# jr-support.net
KiCad netlist of a schematic drawn in EAGLE
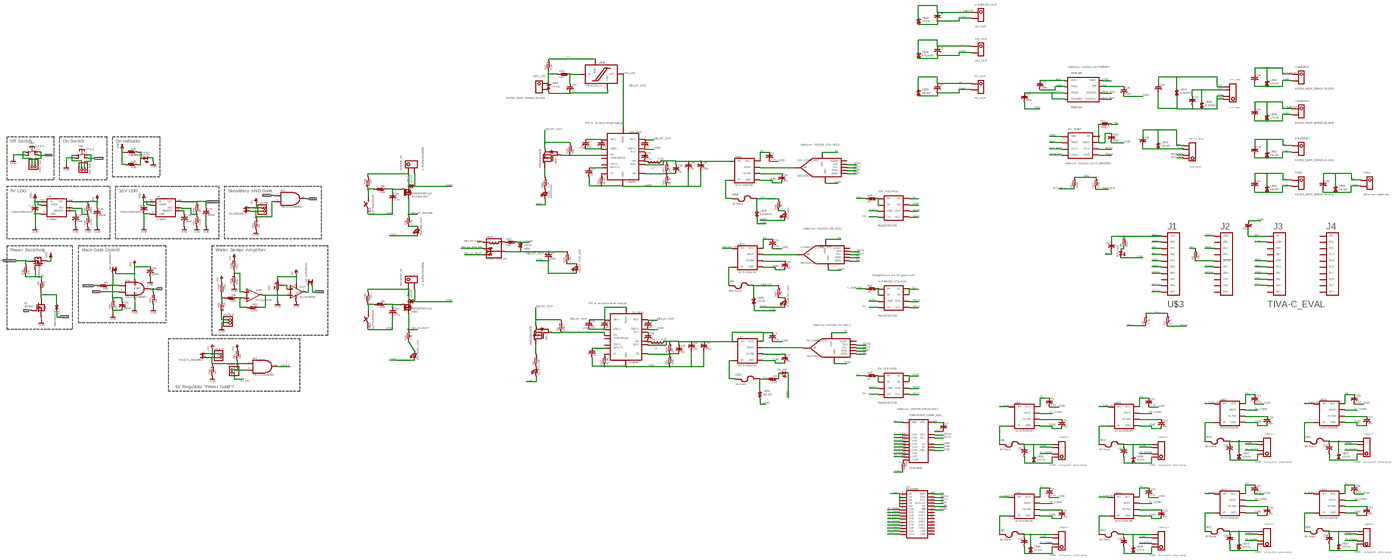
[diagram p0: schematic, sheet 1, overview]
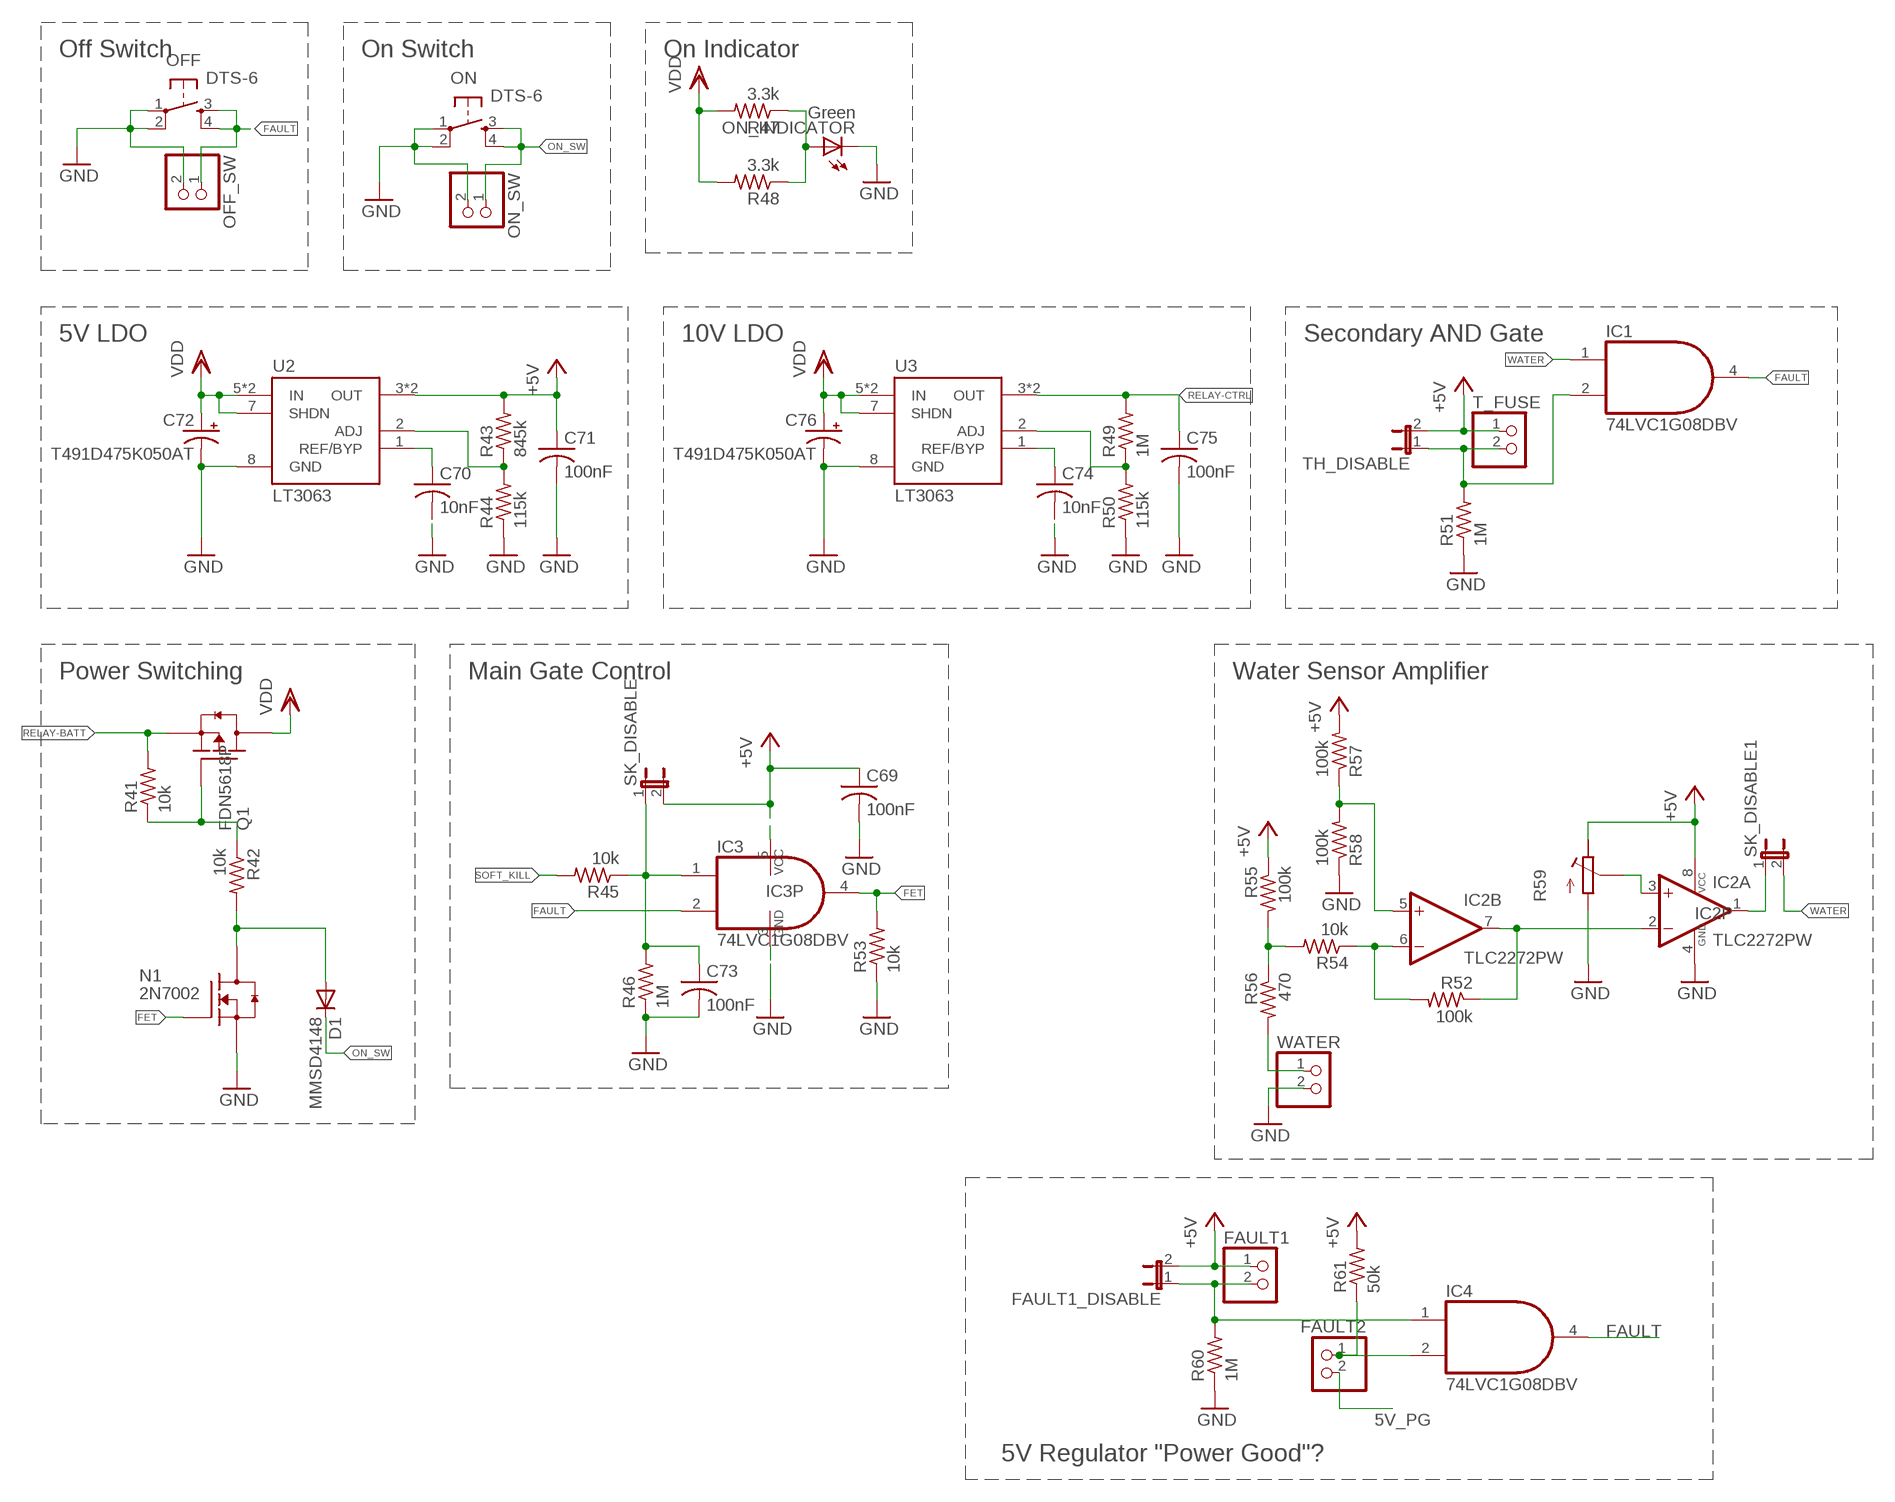
[diagram p1: schematic, sheet 1, part 1 of 4]
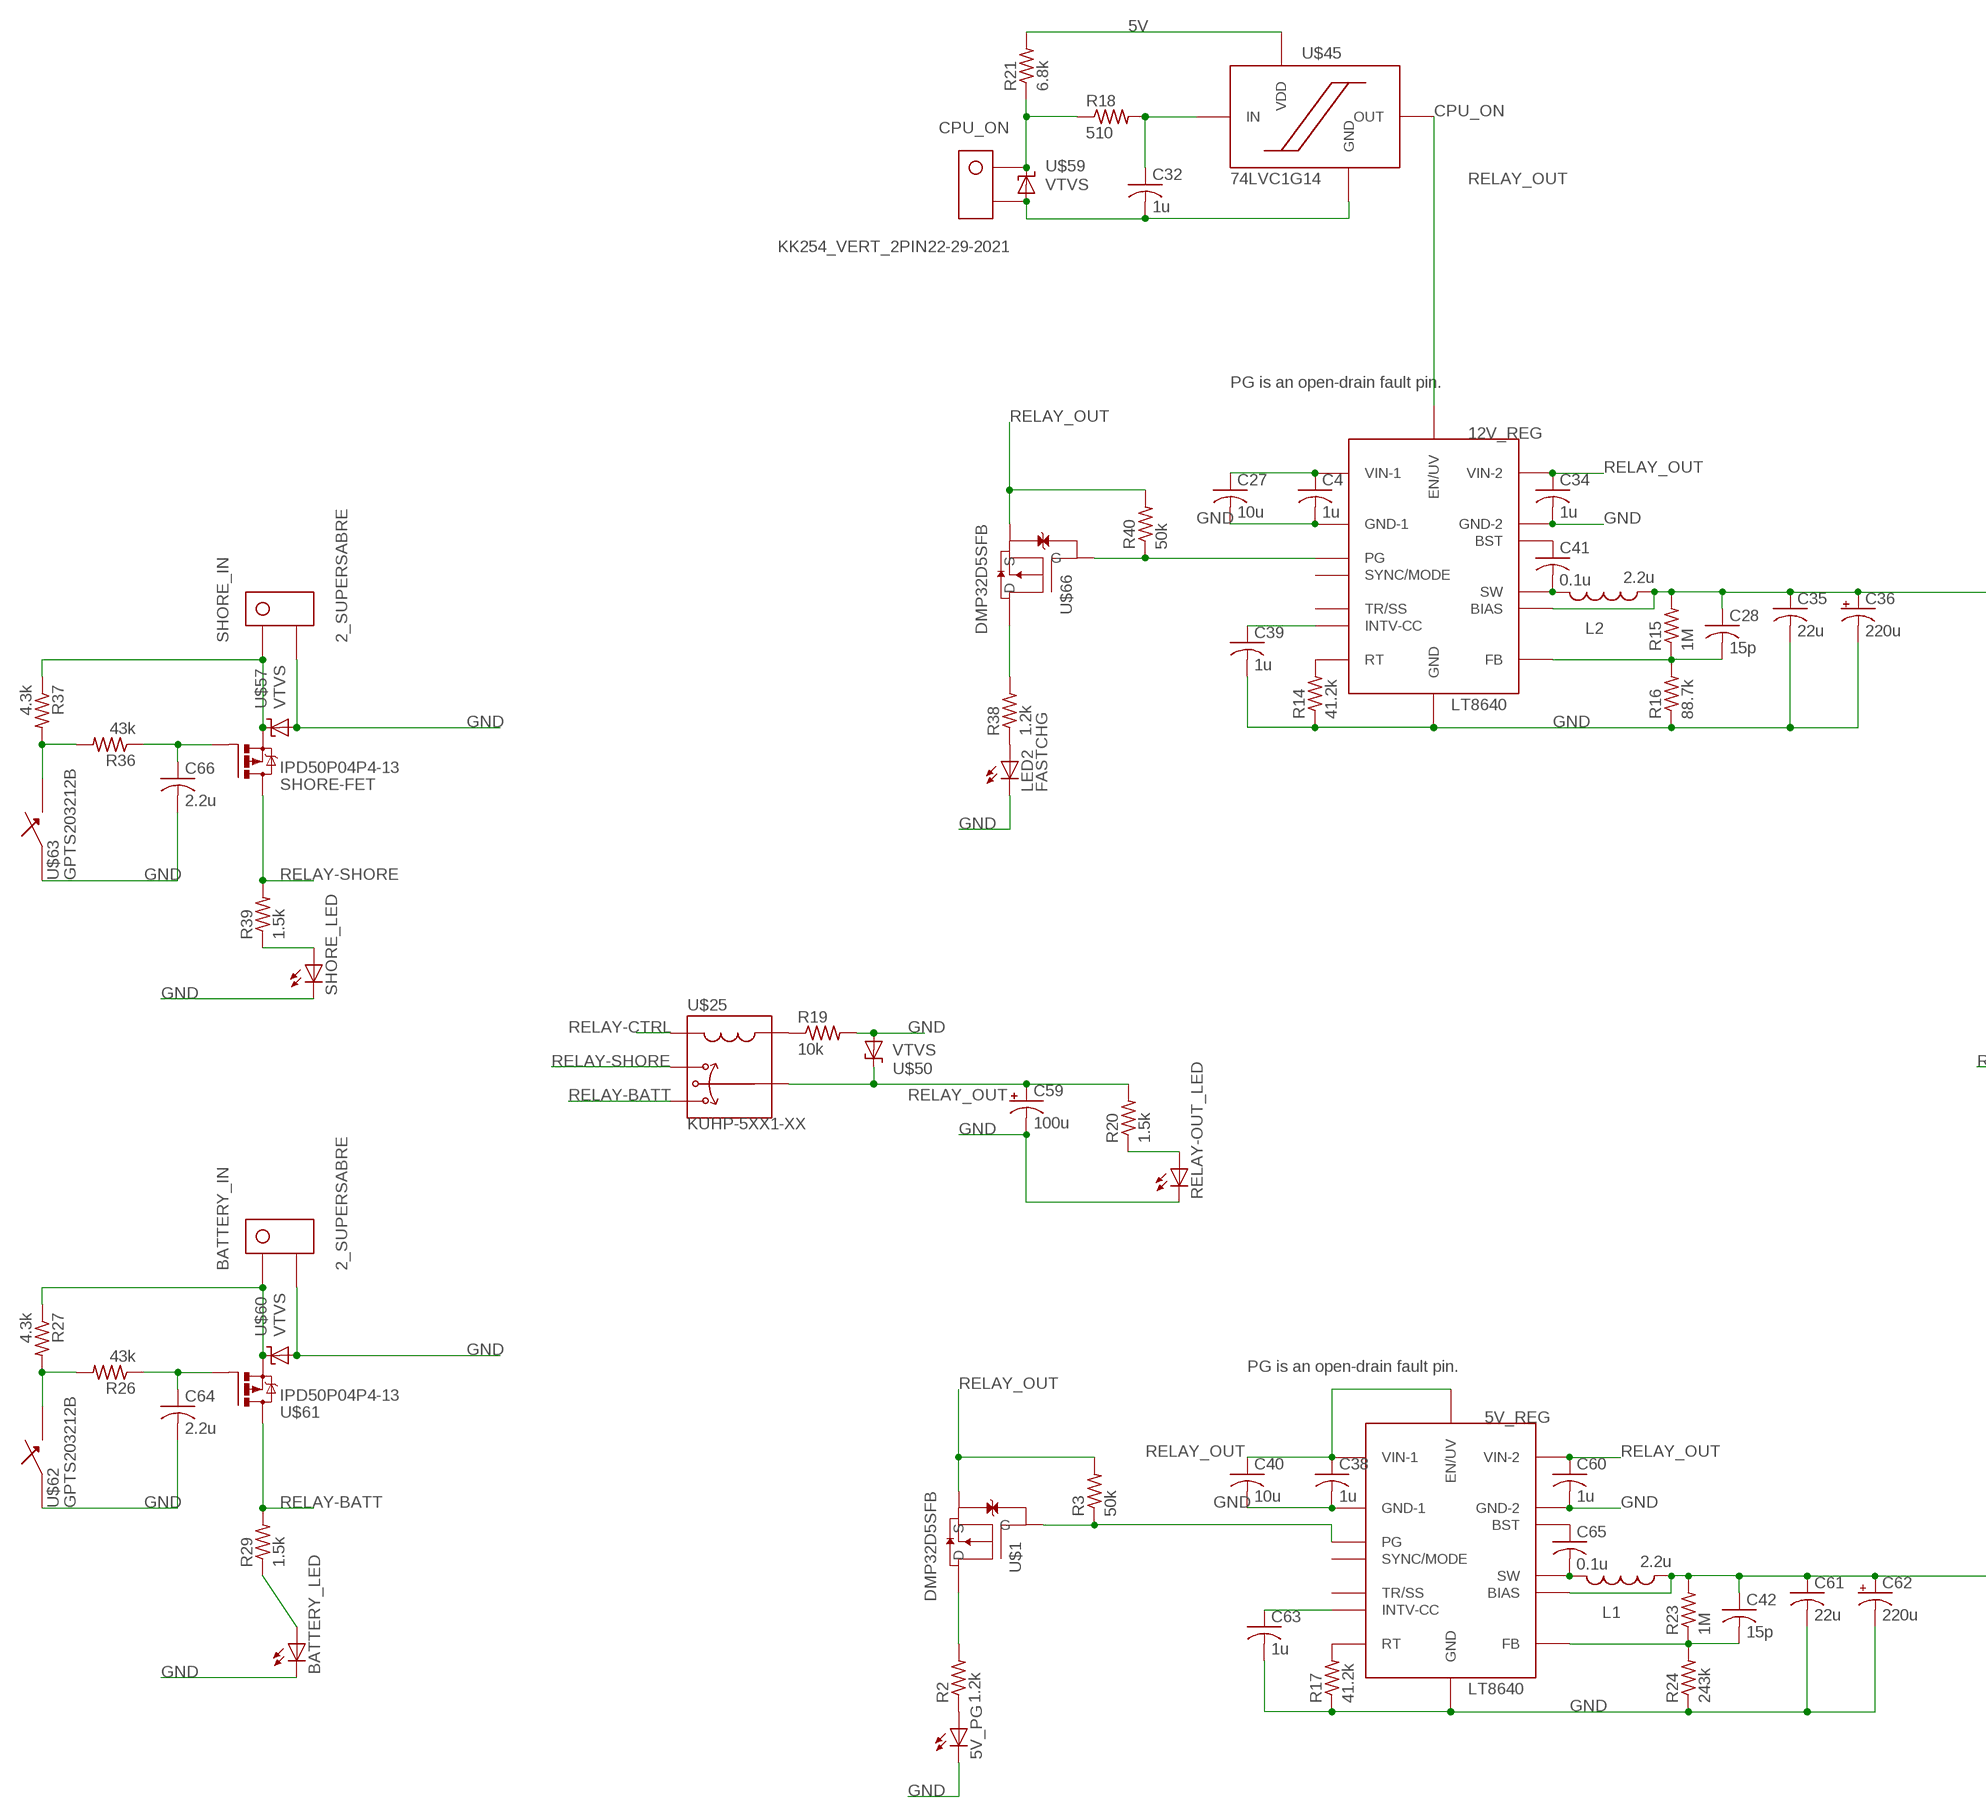
[diagram p2: schematic, sheet 1, part 2 of 4]
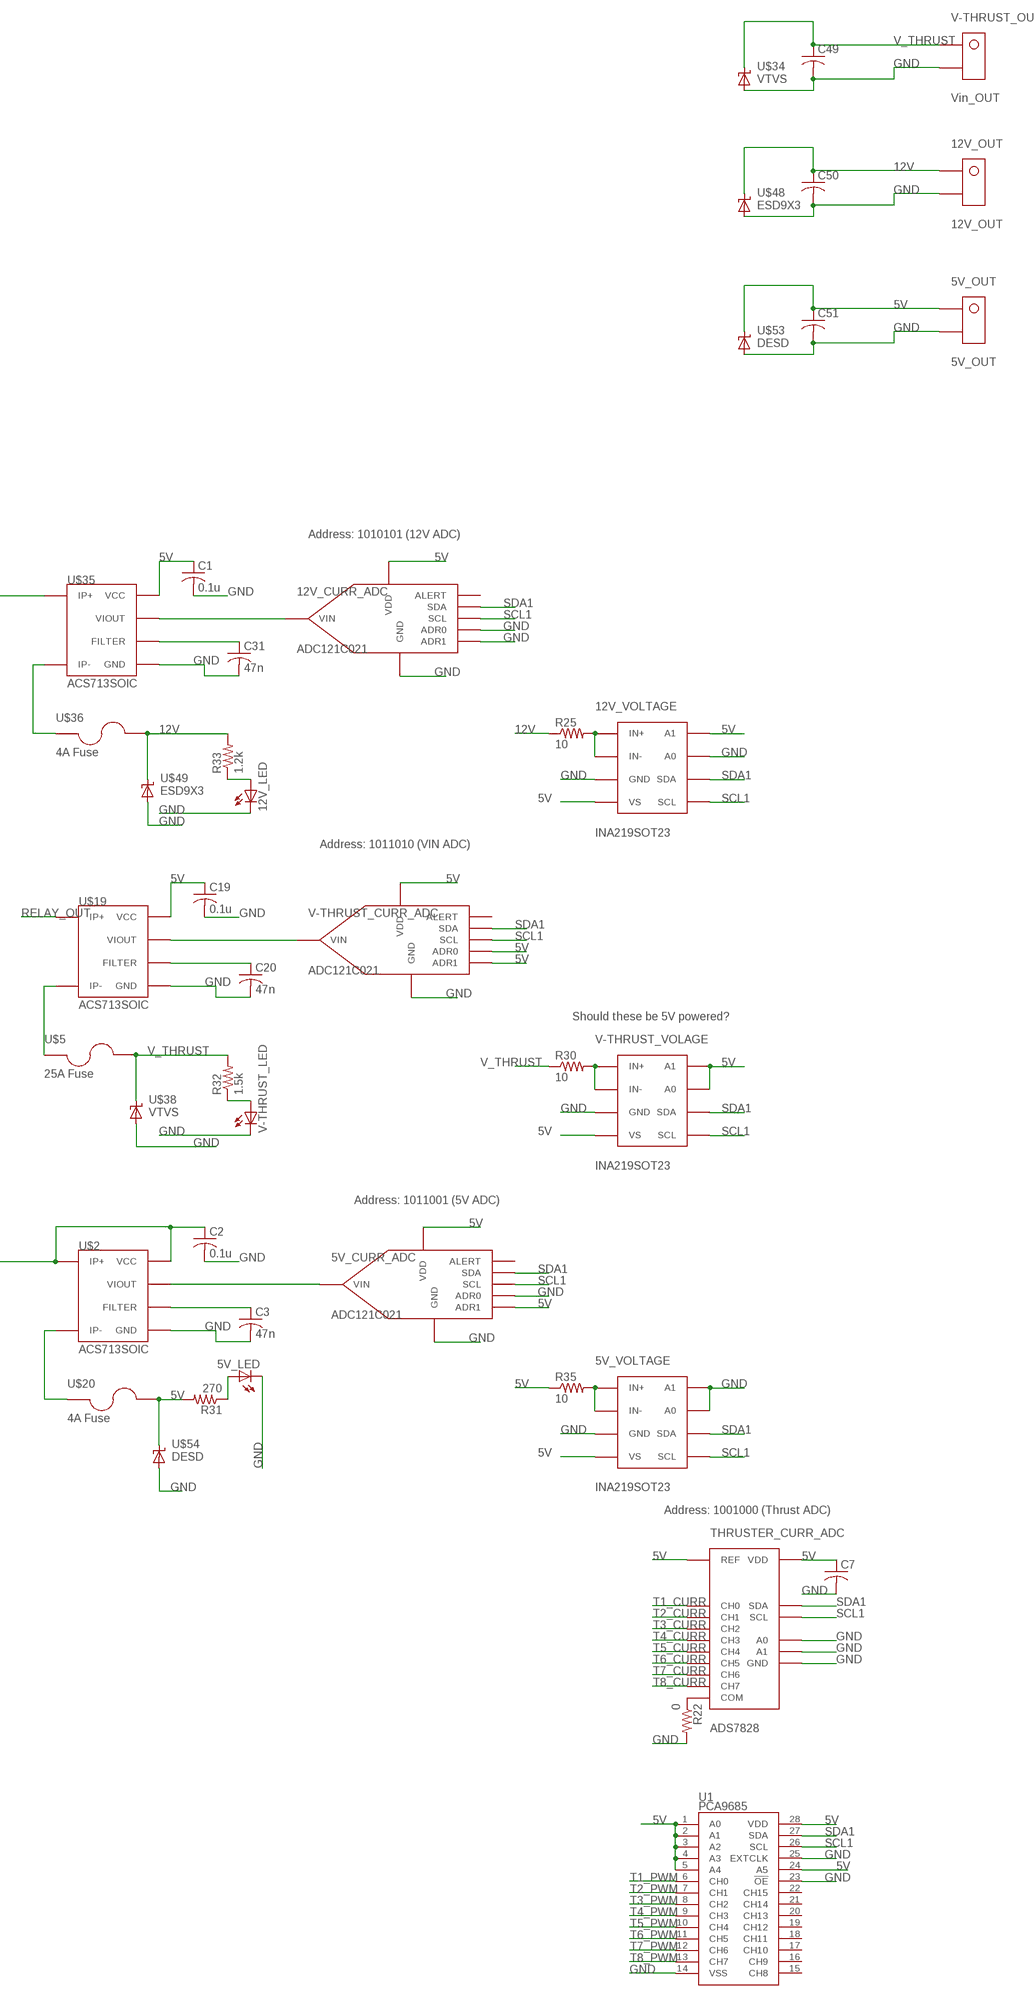
[diagram p3: schematic, sheet 1, part 3 of 4]
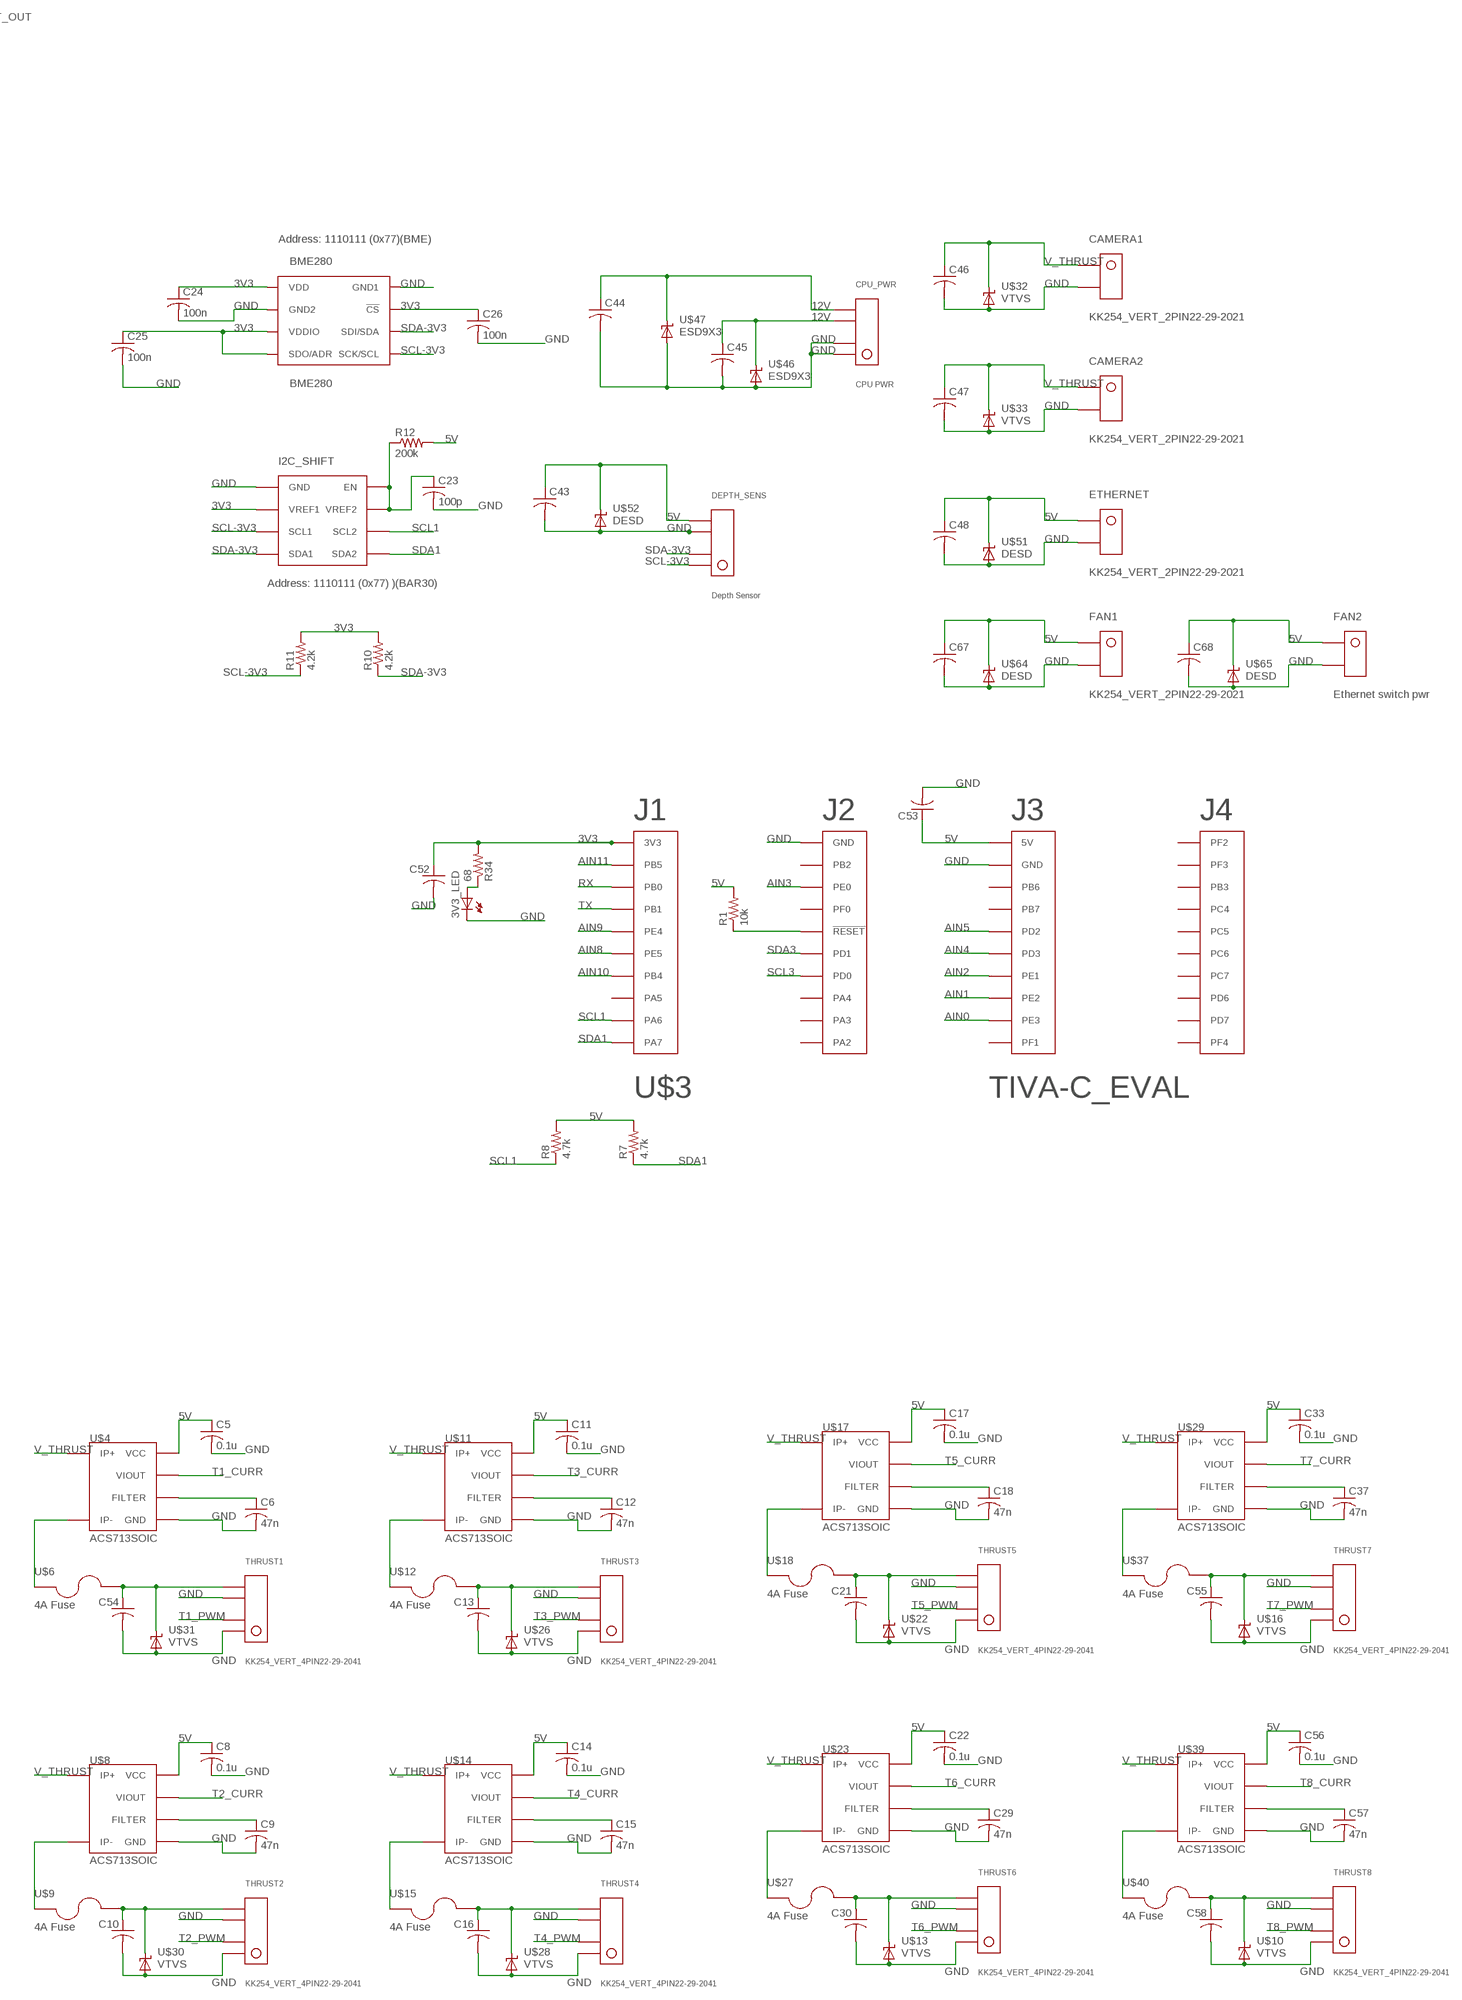
[diagram p4: schematic, sheet 1, part 4 of 4]

(export (version "E")
  (design (tool "Eeschema 10.0.6"))
  (components
    (comp (ref "3V3_LED")
      (value "0805_LED")
      (footprint "eagle-import:0805")
      (libsource (lib "eagle-import") (part "0805_LED"))
    )
    (comp (ref "5V_CURR_ADC")
      (value "ADC121C021")
      (footprint "eagle-import:VSSOP-8")
      (libsource (lib "eagle-import") (part "ADC121C021"))
    )
    (comp (ref "5V_LED")
      (value "0805_LED")
      (footprint "eagle-import:0805")
      (libsource (lib "eagle-import") (part "0805_LED"))
    )
    (comp (ref "5V_OUT")
      (value "5V_OUT")
      (footprint "eagle-import:KK254_VERT_2PIN")
      (libsource (lib "eagle-import") (part "KK254_VERT_2PIN22-29-2021"))
    )
    (comp (ref "5V_PG")
      (value "LEDCHIP-LED0805")
      (footprint "eagle-import:CHIP-LED0805")
      (libsource (lib "eagle-import") (part "LEDCHIP-LED0805"))
    )
    (comp (ref "5V_REG")
      (value "LT8640")
      (footprint "eagle-import:QFN18-3X4")
      (libsource (lib "eagle-import") (part "LT8640"))
    )
    (comp (ref "5V_VOLTAGE")
      (value "INA219SOT23")
      (footprint "eagle-import:SOT-23-8")
      (libsource (lib "eagle-import") (part "INA219SOT23"))
    )
    (comp (ref "12V_CURR_ADC")
      (value "ADC121C021")
      (footprint "eagle-import:VSSOP-8")
      (libsource (lib "eagle-import") (part "ADC121C021"))
    )
    (comp (ref "12V_LED")
      (value "0805_LED")
      (footprint "eagle-import:0805")
      (libsource (lib "eagle-import") (part "0805_LED"))
    )
    (comp (ref "12V_OUT")
      (value "12V_OUT")
      (footprint "eagle-import:KK254_VERT_2PIN")
      (libsource (lib "eagle-import") (part "KK254_VERT_2PIN22-29-2021"))
    )
    (comp (ref "12V_REG")
      (value "LT8640")
      (footprint "eagle-import:QFN18-3X4")
      (libsource (lib "eagle-import") (part "LT8640"))
    )
    (comp (ref "12V_VOLTAGE")
      (value "INA219SOT23")
      (footprint "eagle-import:SOT-23-8")
      (libsource (lib "eagle-import") (part "INA219SOT23"))
    )
    (comp (ref "BATTERY_IN")
      (value "2_SUPERSABRE")
      (footprint "eagle-import:SUPERSABRE_2CIRCUIT")
      (libsource (lib "eagle-import") (part "2_SUPERSABRE"))
    )
    (comp (ref "BATTERY_LED")
      (value "0805_LED")
      (footprint "eagle-import:0805")
      (libsource (lib "eagle-import") (part "0805_LED"))
    )
    (comp (ref "BME280")
      (value "BME280")
      (footprint "eagle-import:BME280_LGA")
      (libsource (lib "eagle-import") (part "BME280"))
    )
    (comp (ref "C1")
      (value "0.1u")
      (footprint "eagle-import:C0805")
      (libsource (lib "eagle-import") (part "C-USC0805"))
    )
    (comp (ref "C2")
      (value "0.1u")
      (footprint "eagle-import:C0805")
      (libsource (lib "eagle-import") (part "C-USC0805"))
    )
    (comp (ref "C3")
      (value "47n")
      (footprint "eagle-import:C0805")
      (libsource (lib "eagle-import") (part "C-USC0805"))
    )
    (comp (ref "C4")
      (value "1u")
      (footprint "eagle-import:C0805")
      (libsource (lib "eagle-import") (part "C-USC0805"))
    )
    (comp (ref "C5")
      (value "0.1u")
      (footprint "eagle-import:C0805")
      (libsource (lib "eagle-import") (part "C-USC0805"))
    )
    (comp (ref "C6")
      (value "47n")
      (footprint "eagle-import:C0805")
      (libsource (lib "eagle-import") (part "C-USC0805"))
    )
    (comp (ref "C7")
      (value "C-USC0805")
      (footprint "eagle-import:C0805")
      (libsource (lib "eagle-import") (part "C-USC0805"))
    )
    (comp (ref "C8")
      (value "0.1u")
      (footprint "eagle-import:C0805")
      (libsource (lib "eagle-import") (part "C-USC0805"))
    )
    (comp (ref "C9")
      (value "47n")
      (footprint "eagle-import:C0805")
      (libsource (lib "eagle-import") (part "C-USC0805"))
    )
    (comp (ref "C10")
      (value "C-USC0805")
      (footprint "eagle-import:C0805")
      (libsource (lib "eagle-import") (part "C-USC0805"))
    )
    (comp (ref "C11")
      (value "0.1u")
      (footprint "eagle-import:C0805")
      (libsource (lib "eagle-import") (part "C-USC0805"))
    )
    (comp (ref "C12")
      (value "47n")
      (footprint "eagle-import:C0805")
      (libsource (lib "eagle-import") (part "C-USC0805"))
    )
    (comp (ref "C13")
      (value "C-USC0805")
      (footprint "eagle-import:C0805")
      (libsource (lib "eagle-import") (part "C-USC0805"))
    )
    (comp (ref "C14")
      (value "0.1u")
      (footprint "eagle-import:C0805")
      (libsource (lib "eagle-import") (part "C-USC0805"))
    )
    (comp (ref "C15")
      (value "47n")
      (footprint "eagle-import:C0805")
      (libsource (lib "eagle-import") (part "C-USC0805"))
    )
    (comp (ref "C16")
      (value "C-USC0805")
      (footprint "eagle-import:C0805")
      (libsource (lib "eagle-import") (part "C-USC0805"))
    )
    (comp (ref "C17")
      (value "0.1u")
      (footprint "eagle-import:C0805")
      (libsource (lib "eagle-import") (part "C-USC0805"))
    )
    (comp (ref "C18")
      (value "47n")
      (footprint "eagle-import:C0805")
      (libsource (lib "eagle-import") (part "C-USC0805"))
    )
    (comp (ref "C19")
      (value "0.1u")
      (footprint "eagle-import:C0805")
      (libsource (lib "eagle-import") (part "C-USC0805"))
    )
    (comp (ref "C20")
      (value "47n")
      (footprint "eagle-import:C0805")
      (libsource (lib "eagle-import") (part "C-USC0805"))
    )
    (comp (ref "C21")
      (value "C-USC0805")
      (footprint "eagle-import:C0805")
      (libsource (lib "eagle-import") (part "C-USC0805"))
    )
    (comp (ref "C22")
      (value "0.1u")
      (footprint "eagle-import:C0805")
      (libsource (lib "eagle-import") (part "C-USC0805"))
    )
    (comp (ref "C23")
      (value "100p")
      (footprint "eagle-import:C0805")
      (libsource (lib "eagle-import") (part "C-USC0805"))
    )
    (comp (ref "C24")
      (value "100n")
      (footprint "eagle-import:C0805")
      (libsource (lib "eagle-import") (part "C-USC0805"))
    )
    (comp (ref "C25")
      (value "100n")
      (footprint "eagle-import:C0805")
      (libsource (lib "eagle-import") (part "C-USC0805"))
    )
    (comp (ref "C26")
      (value "100n")
      (footprint "eagle-import:C0805")
      (libsource (lib "eagle-import") (part "C-USC0805"))
    )
    (comp (ref "C27")
      (value "10u")
      (footprint "eagle-import:C0805")
      (libsource (lib "eagle-import") (part "C-USC0805"))
    )
    (comp (ref "C28")
      (value "15p")
      (footprint "eagle-import:C0805")
      (libsource (lib "eagle-import") (part "C-USC0805"))
    )
    (comp (ref "C29")
      (value "47n")
      (footprint "eagle-import:C0805")
      (libsource (lib "eagle-import") (part "C-USC0805"))
    )
    (comp (ref "C30")
      (value "C-USC0805")
      (footprint "eagle-import:C0805")
      (libsource (lib "eagle-import") (part "C-USC0805"))
    )
    (comp (ref "C31")
      (value "47n")
      (footprint "eagle-import:C0805")
      (libsource (lib "eagle-import") (part "C-USC0805"))
    )
    (comp (ref "C32")
      (value "1u")
      (footprint "eagle-import:C0805")
      (libsource (lib "eagle-import") (part "C-USC0805"))
    )
    (comp (ref "C33")
      (value "0.1u")
      (footprint "eagle-import:C0805")
      (libsource (lib "eagle-import") (part "C-USC0805"))
    )
    (comp (ref "C34")
      (value "1u")
      (footprint "eagle-import:C0805")
      (libsource (lib "eagle-import") (part "C-USC0805"))
    )
    (comp (ref "C35")
      (value "22u")
      (footprint "eagle-import:C0805")
      (libsource (lib "eagle-import") (part "C-USC0805"))
    )
    (comp (ref "C36")
      (value "220u")
      (footprint "eagle-import:C-F80")
      (libsource (lib "eagle-import") (part "CPOL-USC-F80"))
    )
    (comp (ref "C37")
      (value "47n")
      (footprint "eagle-import:C0805")
      (libsource (lib "eagle-import") (part "C-USC0805"))
    )
    (comp (ref "C38")
      (value "1u")
      (footprint "eagle-import:C0805")
      (libsource (lib "eagle-import") (part "C-USC0805"))
    )
    (comp (ref "C39")
      (value "1u")
      (footprint "eagle-import:C0805")
      (libsource (lib "eagle-import") (part "C-USC0805"))
    )
    (comp (ref "C40")
      (value "10u")
      (footprint "eagle-import:C0805")
      (libsource (lib "eagle-import") (part "C-USC0805"))
    )
    (comp (ref "C41")
      (value "0.1u")
      (footprint "eagle-import:C0805")
      (libsource (lib "eagle-import") (part "C-USC0805"))
    )
    (comp (ref "C42")
      (value "15p")
      (footprint "eagle-import:C0805")
      (libsource (lib "eagle-import") (part "C-USC0805"))
    )
    (comp (ref "C43")
      (value "C-USC0805")
      (footprint "eagle-import:C0805")
      (libsource (lib "eagle-import") (part "C-USC0805"))
    )
    (comp (ref "C44")
      (value "C-USC0805")
      (footprint "eagle-import:C0805")
      (libsource (lib "eagle-import") (part "C-USC0805"))
    )
    (comp (ref "C45")
      (value "C-USC0805")
      (footprint "eagle-import:C0805")
      (libsource (lib "eagle-import") (part "C-USC0805"))
    )
    (comp (ref "C46")
      (value "C-USC0805")
      (footprint "eagle-import:C0805")
      (libsource (lib "eagle-import") (part "C-USC0805"))
    )
    (comp (ref "C47")
      (value "C-USC0805")
      (footprint "eagle-import:C0805")
      (libsource (lib "eagle-import") (part "C-USC0805"))
    )
    (comp (ref "C48")
      (value "C-USC0805")
      (footprint "eagle-import:C0805")
      (libsource (lib "eagle-import") (part "C-USC0805"))
    )
    (comp (ref "C49")
      (value "C-USC0805")
      (footprint "eagle-import:C0805")
      (libsource (lib "eagle-import") (part "C-USC0805"))
    )
    (comp (ref "C50")
      (value "C-USC0805")
      (footprint "eagle-import:C0805")
      (libsource (lib "eagle-import") (part "C-USC0805"))
    )
    (comp (ref "C51")
      (value "C-USC0805")
      (footprint "eagle-import:C0805")
      (libsource (lib "eagle-import") (part "C-USC0805"))
    )
    (comp (ref "C52")
      (value "C-USC0805")
      (footprint "eagle-import:C0805")
      (libsource (lib "eagle-import") (part "C-USC0805"))
    )
    (comp (ref "C53")
      (value "C-USC0805")
      (footprint "eagle-import:C0805")
      (libsource (lib "eagle-import") (part "C-USC0805"))
    )
    (comp (ref "C54")
      (value "C-USC0805")
      (footprint "eagle-import:C0805")
      (libsource (lib "eagle-import") (part "C-USC0805"))
    )
    (comp (ref "C55")
      (value "C-USC0805")
      (footprint "eagle-import:C0805")
      (libsource (lib "eagle-import") (part "C-USC0805"))
    )
    (comp (ref "C56")
      (value "0.1u")
      (footprint "eagle-import:C0805")
      (libsource (lib "eagle-import") (part "C-USC0805"))
    )
    (comp (ref "C57")
      (value "47n")
      (footprint "eagle-import:C0805")
      (libsource (lib "eagle-import") (part "C-USC0805"))
    )
    (comp (ref "C58")
      (value "C-USC0805")
      (footprint "eagle-import:C0805")
      (libsource (lib "eagle-import") (part "C-USC0805"))
    )
    (comp (ref "C59")
      (value "100u")
      (footprint "eagle-import:E3,5-8")
      (libsource (lib "eagle-import") (part "CPOL-USE3.5-8"))
    )
    (comp (ref "C60")
      (value "1u")
      (footprint "eagle-import:C0805")
      (libsource (lib "eagle-import") (part "C-USC0805"))
    )
    (comp (ref "C61")
      (value "22u")
      (footprint "eagle-import:C0805")
      (libsource (lib "eagle-import") (part "C-USC0805"))
    )
    (comp (ref "C62")
      (value "220u")
      (footprint "eagle-import:C-F80")
      (libsource (lib "eagle-import") (part "CPOL-USC-F80"))
    )
    (comp (ref "C63")
      (value "1u")
      (footprint "eagle-import:C0805")
      (libsource (lib "eagle-import") (part "C-USC0805"))
    )
    (comp (ref "C64")
      (value "2.2u")
      (footprint "eagle-import:C0805")
      (libsource (lib "eagle-import") (part "C-USC0805"))
    )
    (comp (ref "C65")
      (value "0.1u")
      (footprint "eagle-import:C0805")
      (libsource (lib "eagle-import") (part "C-USC0805"))
    )
    (comp (ref "C66")
      (value "2.2u")
      (footprint "eagle-import:C0805")
      (libsource (lib "eagle-import") (part "C-USC0805"))
    )
    (comp (ref "C67")
      (value "C-USC0805")
      (footprint "eagle-import:C0805")
      (libsource (lib "eagle-import") (part "C-USC0805"))
    )
    (comp (ref "C68")
      (value "C-USC0805")
      (footprint "eagle-import:C0805")
      (libsource (lib "eagle-import") (part "C-USC0805"))
    )
    (comp (ref "C69")
      (value "100nF")
      (footprint "eagle-import:C0805")
      (libsource (lib "eagle-import") (part "C-USC0805"))
    )
    (comp (ref "C70")
      (value "10nF")
      (footprint "eagle-import:C0805")
      (libsource (lib "eagle-import") (part "C-USC0805"))
    )
    (comp (ref "C71")
      (value "100nF")
      (footprint "eagle-import:C0805")
      (libsource (lib "eagle-import") (part "C-USC0805"))
    )
    (comp (ref "C72")
      (value "T491D475K050AT")
      (footprint "eagle-import:CT7343")
      (libsource (lib "eagle-import") (part "CPOL-USCT7343"))
    )
    (comp (ref "C73")
      (value "100nF")
      (footprint "eagle-import:C0805")
      (libsource (lib "eagle-import") (part "C-USC0805"))
    )
    (comp (ref "C74")
      (value "10nF")
      (footprint "eagle-import:C0805")
      (libsource (lib "eagle-import") (part "C-USC0805"))
    )
    (comp (ref "C75")
      (value "100nF")
      (footprint "eagle-import:C0805")
      (libsource (lib "eagle-import") (part "C-USC0805"))
    )
    (comp (ref "C76")
      (value "T491D475K050AT")
      (footprint "eagle-import:CT7343")
      (libsource (lib "eagle-import") (part "CPOL-USCT7343"))
    )
    (comp (ref "CAMERA1")
      (value "KK254_VERT_2PIN22-29-2021")
      (footprint "eagle-import:KK254_VERT_2PIN")
      (libsource (lib "eagle-import") (part "KK254_VERT_2PIN22-29-2021"))
    )
    (comp (ref "CAMERA2")
      (value "KK254_VERT_2PIN22-29-2021")
      (footprint "eagle-import:KK254_VERT_2PIN")
      (libsource (lib "eagle-import") (part "KK254_VERT_2PIN22-29-2021"))
    )
    (comp (ref "CPU_ON")
      (value "KK254_VERT_2PIN22-29-2021")
      (footprint "eagle-import:KK254_VERT_2PIN")
      (libsource (lib "eagle-import") (part "KK254_VERT_2PIN22-29-2021"))
    )
    (comp (ref "CPU_PWR")
      (value "CPU PWR")
      (footprint "eagle-import:KK254_VERT_4PIN")
      (libsource (lib "eagle-import") (part "KK254_VERT_4PIN22-29-2041"))
    )
    (comp (ref "D1")
      (value "MMSD4148")
      (footprint "eagle-import:SOD123")
      (libsource (lib "eagle-import") (part "DIODE-SOD123"))
    )
    (comp (ref "DEPTH_SENS")
      (value "Depth Sensor")
      (footprint "eagle-import:KK254_VERT_4PIN")
      (libsource (lib "eagle-import") (part "KK254_VERT_4PIN22-29-2041"))
    )
    (comp (ref "ETHERNET")
      (value "KK254_VERT_2PIN22-29-2021")
      (footprint "eagle-import:KK254_VERT_2PIN")
      (libsource (lib "eagle-import") (part "KK254_VERT_2PIN22-29-2021"))
    )
    (comp (ref "FAN1")
      (value "KK254_VERT_2PIN22-29-2021")
      (footprint "eagle-import:KK254_VERT_2PIN")
      (libsource (lib "eagle-import") (part "KK254_VERT_2PIN22-29-2021"))
    )
    (comp (ref "FAN2")
      (value "Ethernet switch pwr")
      (footprint "eagle-import:KK254_VERT_2PIN")
      (libsource (lib "eagle-import") (part "KK254_VERT_2PIN22-29-2021"))
    )
    (comp (ref "FAULT1")
      (value "PINHD-1X2")
      (footprint "eagle-import:1X02")
      (libsource (lib "eagle-import") (part "PINHD-1X2"))
    )
    (comp (ref "FAULT1_DISABLE")
      (value "JP1E")
      (footprint "eagle-import:JP1")
      (libsource (lib "eagle-import") (part "JP1E"))
    )
    (comp (ref "FAULT2")
      (value "PINHD-1X2")
      (footprint "eagle-import:1X02")
      (libsource (lib "eagle-import") (part "PINHD-1X2"))
    )
    (comp (ref "I2C_SHIFT")
      (value "PCA9306DCT")
      (footprint "eagle-import:SM8")
      (libsource (lib "eagle-import") (part "PCA9306DCT"))
    )
    (comp (ref "IC1")
      (value "74LVC1G08DBV")
      (footprint "eagle-import:SOT23-5")
      (libsource (lib "eagle-import") (part "741G08DBVLVC"))
    )
    (comp (ref "IC2")
      (value "TLC2272PW")
      (footprint "eagle-import:TSSOP8")
      (libsource (lib "eagle-import") (part "TLC2272PW"))
    )
    (comp (ref "IC3")
      (value "74LVC1G08DBV")
      (footprint "eagle-import:SOT23-5")
      (libsource (lib "eagle-import") (part "741G08DBVLVC"))
    )
    (comp (ref "IC4")
      (value "74LVC1G08DBV")
      (footprint "eagle-import:SOT23-5")
      (libsource (lib "eagle-import") (part "741G08DBVLVC"))
    )
    (comp (ref "L1")
      (value "2.2u")
      (footprint "eagle-import:L0740")
      (libsource (lib "eagle-import") (part "L-USL0740"))
    )
    (comp (ref "L2")
      (value "2.2u")
      (footprint "eagle-import:L0740")
      (libsource (lib "eagle-import") (part "L-USL0740"))
    )
    (comp (ref "LED2")
      (value "FASTCHG")
      (footprint "eagle-import:CHIP-LED0805")
      (libsource (lib "eagle-import") (part "LEDCHIP-LED0805"))
    )
    (comp (ref "N1")
      (value "2N7002")
      (footprint "eagle-import:SOT23")
      (libsource (lib "eagle-import") (part "2N7002"))
    )
    (comp (ref "OFF")
      (value "DTS-6")
      (footprint "eagle-import:DTS-6")
      (libsource (lib "eagle-import") (part "DTS-6"))
    )
    (comp (ref "OFF_SW")
      (value "PINHD-1X2")
      (footprint "eagle-import:1X02")
      (libsource (lib "eagle-import") (part "PINHD-1X2"))
    )
    (comp (ref "ON")
      (value "DTS-6")
      (footprint "eagle-import:DTS-6")
      (libsource (lib "eagle-import") (part "DTS-6"))
    )
    (comp (ref "ON_INDICATOR")
      (value "Green")
      (footprint "eagle-import:CHIP-LED0805")
      (libsource (lib "eagle-import") (part "LEDCHIP-LED0805"))
    )
    (comp (ref "ON_SW")
      (value "PINHD-1X2")
      (footprint "eagle-import:1X02")
      (libsource (lib "eagle-import") (part "PINHD-1X2"))
    )
    (comp (ref "Q1")
      (value "FDN5618P")
      (footprint "eagle-import:SOT23")
      (libsource (lib "eagle-import") (part "FDN5618P"))
    )
    (comp (ref "R1")
      (value "10k")
      (footprint "eagle-import:R0805")
      (libsource (lib "eagle-import") (part "R-US_R0805"))
    )
    (comp (ref "R2")
      (value "1.2k")
      (footprint "eagle-import:R0805")
      (libsource (lib "eagle-import") (part "R-US_R0805"))
    )
    (comp (ref "R3")
      (value "50k")
      (footprint "eagle-import:R0805")
      (libsource (lib "eagle-import") (part "R-US_R0805"))
    )
    (comp (ref "R7")
      (value "4.7k")
      (footprint "eagle-import:R0805")
      (libsource (lib "eagle-import") (part "R-US_R0805"))
    )
    (comp (ref "R8")
      (value "4.7k")
      (footprint "eagle-import:R0805")
      (libsource (lib "eagle-import") (part "R-US_R0805"))
    )
    (comp (ref "R10")
      (value "4.2k")
      (footprint "eagle-import:R0805")
      (libsource (lib "eagle-import") (part "R-US_R0805"))
    )
    (comp (ref "R11")
      (value "4.2k")
      (footprint "eagle-import:R0805")
      (libsource (lib "eagle-import") (part "R-US_R0805"))
    )
    (comp (ref "R12")
      (value "200k")
      (footprint "eagle-import:R0805")
      (libsource (lib "eagle-import") (part "R-US_R0805"))
    )
    (comp (ref "R14")
      (value "41.2k")
      (footprint "eagle-import:R0805")
      (libsource (lib "eagle-import") (part "R-US_R0805"))
    )
    (comp (ref "R15")
      (value "1M")
      (footprint "eagle-import:R0805")
      (libsource (lib "eagle-import") (part "R-US_R0805"))
    )
    (comp (ref "R16")
      (value "88.7k")
      (footprint "eagle-import:R0805")
      (libsource (lib "eagle-import") (part "R-US_R0805"))
    )
    (comp (ref "R17")
      (value "41.2k")
      (footprint "eagle-import:R0805")
      (libsource (lib "eagle-import") (part "R-US_R0805"))
    )
    (comp (ref "R18")
      (value "510")
      (footprint "eagle-import:R0805")
      (libsource (lib "eagle-import") (part "R-US_R0805"))
    )
    (comp (ref "R19")
      (value "10k")
      (footprint "eagle-import:R0805")
      (libsource (lib "eagle-import") (part "R-US_R0805"))
    )
    (comp (ref "R20")
      (value "1.5k")
      (footprint "eagle-import:R0805")
      (libsource (lib "eagle-import") (part "R-US_R0805"))
    )
    (comp (ref "R21")
      (value "6.8k")
      (footprint "eagle-import:R0805")
      (libsource (lib "eagle-import") (part "R-US_R0805"))
    )
    (comp (ref "R22")
      (value "0")
      (footprint "eagle-import:R0805")
      (libsource (lib "eagle-import") (part "R-US_R0805"))
    )
    (comp (ref "R23")
      (value "1M")
      (footprint "eagle-import:R0805")
      (libsource (lib "eagle-import") (part "R-US_R0805"))
    )
    (comp (ref "R24")
      (value "243k")
      (footprint "eagle-import:R0805")
      (libsource (lib "eagle-import") (part "R-US_R0805"))
    )
    (comp (ref "R25")
      (value "10")
      (footprint "eagle-import:R0805")
      (libsource (lib "eagle-import") (part "R-US_R0805"))
    )
    (comp (ref "R26")
      (value "43k")
      (footprint "eagle-import:R0805")
      (libsource (lib "eagle-import") (part "R-US_R0805"))
    )
    (comp (ref "R27")
      (value "4.3k")
      (footprint "eagle-import:R0805")
      (libsource (lib "eagle-import") (part "R-US_R0805"))
    )
    (comp (ref "R29")
      (value "1.5k")
      (footprint "eagle-import:R0805")
      (libsource (lib "eagle-import") (part "R-US_R0805"))
    )
    (comp (ref "R30")
      (value "10")
      (footprint "eagle-import:R0805")
      (libsource (lib "eagle-import") (part "R-US_R0805"))
    )
    (comp (ref "R31")
      (value "270")
      (footprint "eagle-import:R0805")
      (libsource (lib "eagle-import") (part "R-US_R0805"))
    )
    (comp (ref "R32")
      (value "1.5k")
      (footprint "eagle-import:R0805")
      (libsource (lib "eagle-import") (part "R-US_R0805"))
    )
    (comp (ref "R33")
      (value "1.2k")
      (footprint "eagle-import:R0805")
      (libsource (lib "eagle-import") (part "R-US_R0805"))
    )
    (comp (ref "R34")
      (value "68")
      (footprint "eagle-import:R0805")
      (libsource (lib "eagle-import") (part "R-US_R0805"))
    )
    (comp (ref "R35")
      (value "10")
      (footprint "eagle-import:R0805")
      (libsource (lib "eagle-import") (part "R-US_R0805"))
    )
    (comp (ref "R36")
      (value "43k")
      (footprint "eagle-import:R0805")
      (libsource (lib "eagle-import") (part "R-US_R0805"))
    )
    (comp (ref "R37")
      (value "4.3k")
      (footprint "eagle-import:R0805")
      (libsource (lib "eagle-import") (part "R-US_R0805"))
    )
    (comp (ref "R38")
      (value "1.2k")
      (footprint "eagle-import:R0805")
      (libsource (lib "eagle-import") (part "R-US_R0805"))
    )
    (comp (ref "R39")
      (value "1.5k")
      (footprint "eagle-import:R0805")
      (libsource (lib "eagle-import") (part "R-US_R0805"))
    )
    (comp (ref "R40")
      (value "50k")
      (footprint "eagle-import:R0805")
      (libsource (lib "eagle-import") (part "R-US_R0805"))
    )
    (comp (ref "R41")
      (value "10k")
      (footprint "eagle-import:R0805")
      (libsource (lib "eagle-import") (part "R-US_R0805"))
    )
    (comp (ref "R42")
      (value "10k")
      (footprint "eagle-import:R0805")
      (libsource (lib "eagle-import") (part "R-US_R0805"))
    )
    (comp (ref "R43")
      (value "845k")
      (footprint "eagle-import:R0805")
      (libsource (lib "eagle-import") (part "R-US_R0805"))
    )
    (comp (ref "R44")
      (value "115k")
      (footprint "eagle-import:R0805")
      (libsource (lib "eagle-import") (part "R-US_R0805"))
    )
    (comp (ref "R45")
      (value "10k")
      (footprint "eagle-import:R0805")
      (libsource (lib "eagle-import") (part "R-US_R0805"))
    )
    (comp (ref "R46")
      (value "1M")
      (footprint "eagle-import:R0805")
      (libsource (lib "eagle-import") (part "R-US_R0805"))
    )
    (comp (ref "R47")
      (value "3.3k")
      (footprint "eagle-import:R0805")
      (libsource (lib "eagle-import") (part "R-US_R0805"))
    )
    (comp (ref "R48")
      (value "3.3k")
      (footprint "eagle-import:R0805")
      (libsource (lib "eagle-import") (part "R-US_R0805"))
    )
    (comp (ref "R49")
      (value "1M")
      (footprint "eagle-import:R0805")
      (libsource (lib "eagle-import") (part "R-US_R0805"))
    )
    (comp (ref "R50")
      (value "115k")
      (footprint "eagle-import:R0805")
      (libsource (lib "eagle-import") (part "R-US_R0805"))
    )
    (comp (ref "R51")
      (value "1M")
      (footprint "eagle-import:R0805")
      (libsource (lib "eagle-import") (part "R-US_R0805"))
    )
    (comp (ref "R52")
      (value "100k")
      (footprint "eagle-import:R0805")
      (libsource (lib "eagle-import") (part "R-US_R0805"))
    )
    (comp (ref "R53")
      (value "10k")
      (footprint "eagle-import:R0805")
      (libsource (lib "eagle-import") (part "R-US_R0805"))
    )
    (comp (ref "R54")
      (value "10k")
      (footprint "eagle-import:R0805")
      (libsource (lib "eagle-import") (part "R-US_R0805"))
    )
    (comp (ref "R55")
      (value "100k")
      (footprint "eagle-import:R0805")
      (libsource (lib "eagle-import") (part "R-US_R0805"))
    )
    (comp (ref "R56")
      (value "470")
      (footprint "eagle-import:R0805")
      (libsource (lib "eagle-import") (part "R-US_R0805"))
    )
    (comp (ref "R57")
      (value "100k")
      (footprint "eagle-import:R0805")
      (libsource (lib "eagle-import") (part "R-US_R0805"))
    )
    (comp (ref "R58")
      (value "100k")
      (footprint "eagle-import:R0805")
      (libsource (lib "eagle-import") (part "R-US_R0805"))
    )
    (comp (ref "R59")
      (value "R-TRIMM3314J")
      (footprint "eagle-import:RTRIM3314J")
      (libsource (lib "eagle-import") (part "R-TRIMM3314J"))
    )
    (comp (ref "R60")
      (value "1M")
      (footprint "eagle-import:R0805")
      (libsource (lib "eagle-import") (part "R-US_R0805"))
    )
    (comp (ref "R61")
      (value "50k")
      (footprint "eagle-import:R0805")
      (libsource (lib "eagle-import") (part "R-US_R0805"))
    )
    (comp (ref "RELAY-OUT_LED")
      (value "0805_LED")
      (footprint "eagle-import:0805")
      (libsource (lib "eagle-import") (part "0805_LED"))
    )
    (comp (ref "SHORE-FET")
      (value "IPD50P04P4-13")
      (footprint "eagle-import:TO252-3")
      (libsource (lib "eagle-import") (part "IPD50P04P4-13"))
    )
    (comp (ref "SHORE_IN")
      (value "2_SUPERSABRE")
      (footprint "eagle-import:SUPERSABRE_2CIRCUIT")
      (libsource (lib "eagle-import") (part "2_SUPERSABRE"))
    )
    (comp (ref "SHORE_LED")
      (value "0805_LED")
      (footprint "eagle-import:0805")
      (libsource (lib "eagle-import") (part "0805_LED"))
    )
    (comp (ref "SK_DISABLE")
      (value "JP1E")
      (footprint "eagle-import:JP1")
      (libsource (lib "eagle-import") (part "JP1E"))
    )
    (comp (ref "SK_DISABLE1")
      (value "JP1E")
      (footprint "eagle-import:JP1")
      (libsource (lib "eagle-import") (part "JP1E"))
    )
    (comp (ref "THRUST1")
      (value "KK254_VERT_4PIN22-29-2041")
      (footprint "eagle-import:KK254_VERT_4PIN")
      (libsource (lib "eagle-import") (part "KK254_VERT_4PIN22-29-2041"))
    )
    (comp (ref "THRUST2")
      (value "KK254_VERT_4PIN22-29-2041")
      (footprint "eagle-import:KK254_VERT_4PIN")
      (libsource (lib "eagle-import") (part "KK254_VERT_4PIN22-29-2041"))
    )
    (comp (ref "THRUST3")
      (value "KK254_VERT_4PIN22-29-2041")
      (footprint "eagle-import:KK254_VERT_4PIN")
      (libsource (lib "eagle-import") (part "KK254_VERT_4PIN22-29-2041"))
    )
    (comp (ref "THRUST4")
      (value "KK254_VERT_4PIN22-29-2041")
      (footprint "eagle-import:KK254_VERT_4PIN")
      (libsource (lib "eagle-import") (part "KK254_VERT_4PIN22-29-2041"))
    )
    (comp (ref "THRUST5")
      (value "KK254_VERT_4PIN22-29-2041")
      (footprint "eagle-import:KK254_VERT_4PIN")
      (libsource (lib "eagle-import") (part "KK254_VERT_4PIN22-29-2041"))
    )
    (comp (ref "THRUST6")
      (value "KK254_VERT_4PIN22-29-2041")
      (footprint "eagle-import:KK254_VERT_4PIN")
      (libsource (lib "eagle-import") (part "KK254_VERT_4PIN22-29-2041"))
    )
    (comp (ref "THRUST7")
      (value "KK254_VERT_4PIN22-29-2041")
      (footprint "eagle-import:KK254_VERT_4PIN")
      (libsource (lib "eagle-import") (part "KK254_VERT_4PIN22-29-2041"))
    )
    (comp (ref "THRUST8")
      (value "KK254_VERT_4PIN22-29-2041")
      (footprint "eagle-import:KK254_VERT_4PIN")
      (libsource (lib "eagle-import") (part "KK254_VERT_4PIN22-29-2041"))
    )
    (comp (ref "THRUSTER_CURR_ADC")
      (value "ADS7828")
      (footprint "eagle-import:TSSOP16")
      (libsource (lib "eagle-import") (part "ADS7828"))
    )
    (comp (ref "TH_DISABLE")
      (value "JP1E")
      (footprint "eagle-import:JP1")
      (libsource (lib "eagle-import") (part "JP1E"))
    )
    (comp (ref "T_FUSE")
      (value "PINHD-1X2")
      (footprint "eagle-import:1X02")
      (libsource (lib "eagle-import") (part "PINHD-1X2"))
    )
    (comp (ref "U$1")
      (value "DMP32D5SFB")
      (footprint "eagle-import:AP02002")
      (libsource (lib "eagle-import") (part "DMP32D5SFB"))
    )
    (comp (ref "U$2")
      (value "ACS713SOIC")
      (footprint "eagle-import:ACS713-SOIC")
      (libsource (lib "eagle-import") (part "ACS713SOIC"))
    )
    (comp (ref "U$3")
      (value "TIVA-C_EVAL")
      (footprint "eagle-import:TIVA-C_EVAL")
      (libsource (lib "eagle-import") (part "TIVA-C_EVAL"))
    )
    (comp (ref "U$4")
      (value "ACS713SOIC")
      (footprint "eagle-import:ACS713-SOIC")
      (libsource (lib "eagle-import") (part "ACS713SOIC"))
    )
    (comp (ref "U$5")
      (value "25A Fuse")
      (footprint "eagle-import:1.25__FUSECLIPS")
      (libsource (lib "eagle-import") (part "BOWED-1.25{dblquote}-FUSECLIPS"))
    )
    (comp (ref "U$6")
      (value "4A Fuse")
      (footprint "eagle-import:154-OMNI-BLOK")
      (libsource (lib "eagle-import") (part "154-OMNI_BLOK"))
    )
    (comp (ref "U$8")
      (value "ACS713SOIC")
      (footprint "eagle-import:ACS713-SOIC")
      (libsource (lib "eagle-import") (part "ACS713SOIC"))
    )
    (comp (ref "U$9")
      (value "4A Fuse")
      (footprint "eagle-import:154-OMNI-BLOK")
      (libsource (lib "eagle-import") (part "154-OMNI_BLOK"))
    )
    (comp (ref "U$10")
      (value "VTVS")
      (footprint "eagle-import:DO-219AB")
      (libsource (lib "eagle-import") (part "VTVS"))
    )
    (comp (ref "U$11")
      (value "ACS713SOIC")
      (footprint "eagle-import:ACS713-SOIC")
      (libsource (lib "eagle-import") (part "ACS713SOIC"))
    )
    (comp (ref "U$12")
      (value "4A Fuse")
      (footprint "eagle-import:154-OMNI-BLOK")
      (libsource (lib "eagle-import") (part "154-OMNI_BLOK"))
    )
    (comp (ref "U$13")
      (value "VTVS")
      (footprint "eagle-import:DO-219AB")
      (libsource (lib "eagle-import") (part "VTVS"))
    )
    (comp (ref "U$14")
      (value "ACS713SOIC")
      (footprint "eagle-import:ACS713-SOIC")
      (libsource (lib "eagle-import") (part "ACS713SOIC"))
    )
    (comp (ref "U$15")
      (value "4A Fuse")
      (footprint "eagle-import:154-OMNI-BLOK")
      (libsource (lib "eagle-import") (part "154-OMNI_BLOK"))
    )
    (comp (ref "U$16")
      (value "VTVS")
      (footprint "eagle-import:DO-219AB")
      (libsource (lib "eagle-import") (part "VTVS"))
    )
    (comp (ref "U$17")
      (value "ACS713SOIC")
      (footprint "eagle-import:ACS713-SOIC")
      (libsource (lib "eagle-import") (part "ACS713SOIC"))
    )
    (comp (ref "U$18")
      (value "4A Fuse")
      (footprint "eagle-import:154-OMNI-BLOK")
      (libsource (lib "eagle-import") (part "154-OMNI_BLOK"))
    )
    (comp (ref "U$19")
      (value "ACS713SOIC")
      (footprint "eagle-import:ACS713-SOIC")
      (libsource (lib "eagle-import") (part "ACS713SOIC"))
    )
    (comp (ref "U$20")
      (value "4A Fuse")
      (footprint "eagle-import:154-OMNI-BLOK")
      (libsource (lib "eagle-import") (part "154-OMNI_BLOK"))
    )
    (comp (ref "U$22")
      (value "VTVS")
      (footprint "eagle-import:DO-219AB")
      (libsource (lib "eagle-import") (part "VTVS"))
    )
    (comp (ref "U$23")
      (value "ACS713SOIC")
      (footprint "eagle-import:ACS713-SOIC")
      (libsource (lib "eagle-import") (part "ACS713SOIC"))
    )
    (comp (ref "U$25")
      (value "KUHP-5XX1-XX")
      (footprint "eagle-import:KUHP_6.35MM-QUICK-CONNECT")
      (libsource (lib "eagle-import") (part "KUHP-5XX1-XX"))
    )
    (comp (ref "U$26")
      (value "VTVS")
      (footprint "eagle-import:DO-219AB")
      (libsource (lib "eagle-import") (part "VTVS"))
    )
    (comp (ref "U$27")
      (value "4A Fuse")
      (footprint "eagle-import:154-OMNI-BLOK")
      (libsource (lib "eagle-import") (part "154-OMNI_BLOK"))
    )
    (comp (ref "U$28")
      (value "VTVS")
      (footprint "eagle-import:DO-219AB")
      (libsource (lib "eagle-import") (part "VTVS"))
    )
    (comp (ref "U$29")
      (value "ACS713SOIC")
      (footprint "eagle-import:ACS713-SOIC")
      (libsource (lib "eagle-import") (part "ACS713SOIC"))
    )
    (comp (ref "U$30")
      (value "VTVS")
      (footprint "eagle-import:DO-219AB")
      (libsource (lib "eagle-import") (part "VTVS"))
    )
    (comp (ref "U$31")
      (value "VTVS")
      (footprint "eagle-import:DO-219AB")
      (libsource (lib "eagle-import") (part "VTVS"))
    )
    (comp (ref "U$32")
      (value "VTVS")
      (footprint "eagle-import:DO-219AB")
      (libsource (lib "eagle-import") (part "VTVS"))
    )
    (comp (ref "U$33")
      (value "VTVS")
      (footprint "eagle-import:DO-219AB")
      (libsource (lib "eagle-import") (part "VTVS"))
    )
    (comp (ref "U$34")
      (value "VTVS")
      (footprint "eagle-import:DO-219AB")
      (libsource (lib "eagle-import") (part "VTVS"))
    )
    (comp (ref "U$35")
      (value "ACS713SOIC")
      (footprint "eagle-import:ACS713-SOIC")
      (libsource (lib "eagle-import") (part "ACS713SOIC"))
    )
    (comp (ref "U$36")
      (value "4A Fuse")
      (footprint "eagle-import:154-OMNI-BLOK")
      (libsource (lib "eagle-import") (part "154-OMNI_BLOK"))
    )
    (comp (ref "U$37")
      (value "4A Fuse")
      (footprint "eagle-import:154-OMNI-BLOK")
      (libsource (lib "eagle-import") (part "154-OMNI_BLOK"))
    )
    (comp (ref "U$38")
      (value "VTVS")
      (footprint "eagle-import:DO-219AB")
      (libsource (lib "eagle-import") (part "VTVS"))
    )
    (comp (ref "U$39")
      (value "ACS713SOIC")
      (footprint "eagle-import:ACS713-SOIC")
      (libsource (lib "eagle-import") (part "ACS713SOIC"))
    )
    (comp (ref "U$40")
      (value "4A Fuse")
      (footprint "eagle-import:154-OMNI-BLOK")
      (libsource (lib "eagle-import") (part "154-OMNI_BLOK"))
    )
    (comp (ref "U$45")
      (value "74LVC1G14")
      (footprint "eagle-import:TSSOP5")
      (libsource (lib "eagle-import") (part "74LVC1G14"))
    )
    (comp (ref "U$46")
      (value "ESD9X3")
      (footprint "eagle-import:SOD-923_SMD")
      (libsource (lib "eagle-import") (part "ESD9X3"))
    )
    (comp (ref "U$47")
      (value "ESD9X3")
      (footprint "eagle-import:SOD-923_SMD")
      (libsource (lib "eagle-import") (part "ESD9X3"))
    )
    (comp (ref "U$48")
      (value "ESD9X3")
      (footprint "eagle-import:SOD-923_SMD")
      (libsource (lib "eagle-import") (part "ESD9X3"))
    )
    (comp (ref "U$49")
      (value "ESD9X3")
      (footprint "eagle-import:SOD-923_SMD")
      (libsource (lib "eagle-import") (part "ESD9X3"))
    )
    (comp (ref "U$50")
      (value "VTVS")
      (footprint "eagle-import:DO-219AB")
      (libsource (lib "eagle-import") (part "VTVS"))
    )
    (comp (ref "U$51")
      (value "DESD")
      (footprint "eagle-import:X1-DFN1006-2")
      (libsource (lib "eagle-import") (part "DESD"))
    )
    (comp (ref "U$52")
      (value "DESD")
      (footprint "eagle-import:X1-DFN1006-2")
      (libsource (lib "eagle-import") (part "DESD"))
    )
    (comp (ref "U$53")
      (value "DESD")
      (footprint "eagle-import:X1-DFN1006-2")
      (libsource (lib "eagle-import") (part "DESD"))
    )
    (comp (ref "U$54")
      (value "DESD")
      (footprint "eagle-import:X1-DFN1006-2")
      (libsource (lib "eagle-import") (part "DESD"))
    )
    (comp (ref "U$57")
      (value "VTVS")
      (footprint "eagle-import:DO-219AB")
      (libsource (lib "eagle-import") (part "VTVS"))
    )
    (comp (ref "U$59")
      (value "VTVS")
      (footprint "eagle-import:DO-219AB")
      (libsource (lib "eagle-import") (part "VTVS"))
    )
    (comp (ref "U$60")
      (value "VTVS")
      (footprint "eagle-import:DO-219AB")
      (libsource (lib "eagle-import") (part "VTVS"))
    )
    (comp (ref "U$61")
      (value "IPD50P04P4-13")
      (footprint "eagle-import:TO252-3")
      (libsource (lib "eagle-import") (part "IPD50P04P4-13"))
    )
    (comp (ref "U$62")
      (value "GPTS203212B")
      (footprint "eagle-import:GPTS203211B")
      (libsource (lib "eagle-import") (part "GPTS203212B"))
    )
    (comp (ref "U$63")
      (value "GPTS203212B")
      (footprint "eagle-import:GPTS203211B")
      (libsource (lib "eagle-import") (part "GPTS203212B"))
    )
    (comp (ref "U$64")
      (value "DESD")
      (footprint "eagle-import:X1-DFN1006-2")
      (libsource (lib "eagle-import") (part "DESD"))
    )
    (comp (ref "U$65")
      (value "DESD")
      (footprint "eagle-import:X1-DFN1006-2")
      (libsource (lib "eagle-import") (part "DESD"))
    )
    (comp (ref "U$66")
      (value "DMP32D5SFB")
      (footprint "eagle-import:AP02002")
      (libsource (lib "eagle-import") (part "DMP32D5SFB"))
    )
    (comp (ref "U1")
      (value "PCA9685")
      (footprint "eagle-import:TSSOP-28_4MM")
      (libsource (lib "eagle-import") (part "PCA9685"))
    )
    (comp (ref "U2")
      (value "LT3063")
      (footprint "eagle-import:MSOP8")
      (libsource (lib "eagle-import") (part "LT3063"))
    )
    (comp (ref "U3")
      (value "LT3063")
      (footprint "eagle-import:MSOP8")
      (libsource (lib "eagle-import") (part "LT3063"))
    )
    (comp (ref "V-THRUST_CURR_ADC")
      (value "ADC121C021")
      (footprint "eagle-import:VSSOP-8")
      (libsource (lib "eagle-import") (part "ADC121C021"))
    )
    (comp (ref "V-THRUST_LED")
      (value "0805_LED")
      (footprint "eagle-import:0805")
      (libsource (lib "eagle-import") (part "0805_LED"))
    )
    (comp (ref "V-THRUST_OUT")
      (value "Vin_OUT")
      (footprint "eagle-import:KK254_VERT_2PIN")
      (libsource (lib "eagle-import") (part "KK254_VERT_2PIN22-29-2021"))
    )
    (comp (ref "V-THRUST_VOLAGE")
      (value "INA219SOT23")
      (footprint "eagle-import:SOT-23-8")
      (libsource (lib "eagle-import") (part "INA219SOT23"))
    )
    (comp (ref "WATER")
      (value "PINHD-1X2")
      (footprint "eagle-import:1X02")
      (libsource (lib "eagle-import") (part "PINHD-1X2"))
    )
  )
  (nets
    (net (code "1") (name "+5V") (class "Default")
      (node (ref "C69") (pin "1") (pinfunction "1_1") (pintype "passive"))
      (node (ref "C71") (pin "1") (pinfunction "1_1") (pintype "passive"))
      (node (ref "FAULT1") (pin "1") (pinfunction "1_1") (pintype "passive"))
      (node (ref "FAULT1_DISABLE") (pin "2") (pinfunction "2_2") (pintype "passive"))
      (node (ref "IC2") (pin "8") (pinfunction "VCC_8") (pintype "power_in"))
      (node (ref "IC3") (pin "5") (pinfunction "VCC_5") (pintype "power_in"))
      (node (ref "R43") (pin "2") (pinfunction "2_2") (pintype "passive"))
      (node (ref "R55") (pin "1") (pinfunction "1_1") (pintype "passive"))
      (node (ref "R57") (pin "2") (pinfunction "2_2") (pintype "passive"))
      (node (ref "R59") (pin "3") (pinfunction "A_3") (pintype "passive"))
      (node (ref "R61") (pin "2") (pinfunction "2_2") (pintype "passive"))
      (node (ref "SK_DISABLE") (pin "2") (pinfunction "2_2") (pintype "passive"))
      (node (ref "TH_DISABLE") (pin "2") (pinfunction "2_2") (pintype "passive"))
      (node (ref "T_FUSE") (pin "1") (pinfunction "1_1") (pintype "passive"))
      (node (ref "U2") (pin "3") (pinfunction "OUT_3") (pintype "bidirectional"))
      (node (ref "U2") (pin "4") (pinfunction "OUT_4") (pintype "bidirectional"))
    )
    (net (code "2") (name "/3V3") (class "Default")
      (node (ref "BME280") (pin "P$2") (pinfunction "~{CS}_P$2") (pintype "bidirectional"))
      (node (ref "BME280") (pin "P$5") (pinfunction "SDO/ADR_P$5") (pintype "bidirectional"))
      (node (ref "BME280") (pin "P$6") (pinfunction "VDDIO_P$6") (pintype "bidirectional"))
      (node (ref "BME280") (pin "P$8") (pinfunction "VDD_P$8") (pintype "bidirectional"))
      (node (ref "C24") (pin "1") (pinfunction "1_1") (pintype "passive"))
      (node (ref "C25") (pin "1") (pinfunction "1_1") (pintype "passive"))
      (node (ref "C26") (pin "1") (pinfunction "1_1") (pintype "passive"))
      (node (ref "C52") (pin "1") (pinfunction "1_1") (pintype "passive"))
      (node (ref "I2C_SHIFT") (pin "P$2") (pinfunction "VREF1_P$2") (pintype "bidirectional"))
      (node (ref "R10") (pin "2") (pinfunction "2_2") (pintype "passive"))
      (node (ref "R11") (pin "2") (pinfunction "2_2") (pintype "passive"))
      (node (ref "R34") (pin "2") (pinfunction "2_2") (pintype "passive"))
      (node (ref "U$3") (pin "1-1") (pinfunction "3V3_1-1") (pintype "bidirectional"))
    )
    (net (code "3") (name "/5V") (class "Default")
      (node (ref "12V_CURR_ADC") (pin "P$5") (pinfunction "VDD_P$5") (pintype "bidirectional"))
      (node (ref "12V_VOLTAGE") (pin "P$4") (pinfunction "VS_P$4") (pintype "bidirectional"))
      (node (ref "12V_VOLTAGE") (pin "P$8") (pinfunction "A1_P$8") (pintype "bidirectional"))
      (node (ref "5V_CURR_ADC") (pin "P$5") (pinfunction "VDD_P$5") (pintype "bidirectional"))
      (node (ref "5V_CURR_ADC") (pin "P$6") (pinfunction "ADR1_P$6") (pintype "bidirectional"))
      (node (ref "5V_OUT") (pin "P$1") (pinfunction "P$1_P$1") (pintype "bidirectional"))
      (node (ref "5V_VOLTAGE") (pin "P$4") (pinfunction "VS_P$4") (pintype "bidirectional"))
      (node (ref "C1") (pin "1") (pinfunction "1_1") (pintype "passive"))
      (node (ref "C11") (pin "1") (pinfunction "1_1") (pintype "passive"))
      (node (ref "C14") (pin "1") (pinfunction "1_1") (pintype "passive"))
      (node (ref "C17") (pin "1") (pinfunction "1_1") (pintype "passive"))
      (node (ref "C19") (pin "1") (pinfunction "1_1") (pintype "passive"))
      (node (ref "C22") (pin "1") (pinfunction "1_1") (pintype "passive"))
      (node (ref "C33") (pin "1") (pinfunction "1_1") (pintype "passive"))
      (node (ref "C43") (pin "1") (pinfunction "1_1") (pintype "passive"))
      (node (ref "C48") (pin "1") (pinfunction "1_1") (pintype "passive"))
      (node (ref "C5") (pin "1") (pinfunction "1_1") (pintype "passive"))
      (node (ref "C51") (pin "1") (pinfunction "1_1") (pintype "passive"))
      (node (ref "C53") (pin "1") (pinfunction "1_1") (pintype "passive"))
      (node (ref "C56") (pin "1") (pinfunction "1_1") (pintype "passive"))
      (node (ref "C67") (pin "1") (pinfunction "1_1") (pintype "passive"))
      (node (ref "C68") (pin "1") (pinfunction "1_1") (pintype "passive"))
      (node (ref "C7") (pin "1") (pinfunction "1_1") (pintype "passive"))
      (node (ref "C8") (pin "1") (pinfunction "1_1") (pintype "passive"))
      (node (ref "DEPTH_SENS") (pin "P$4") (pinfunction "P$4_P$4") (pintype "bidirectional"))
      (node (ref "ETHERNET") (pin "P$1") (pinfunction "P$1_P$1") (pintype "bidirectional"))
      (node (ref "FAN1") (pin "P$1") (pinfunction "P$1_P$1") (pintype "bidirectional"))
      (node (ref "FAN2") (pin "P$1") (pinfunction "P$1_P$1") (pintype "bidirectional"))
      (node (ref "R1") (pin "2") (pinfunction "2_2") (pintype "passive"))
      (node (ref "R12") (pin "2") (pinfunction "2_2") (pintype "passive"))
      (node (ref "R21") (pin "2") (pinfunction "2_2") (pintype "passive"))
      (node (ref "R31") (pin "2") (pinfunction "2_2") (pintype "passive"))
      (node (ref "R35") (pin "1") (pinfunction "1_1") (pintype "passive"))
      (node (ref "R7") (pin "2") (pinfunction "2_2") (pintype "passive"))
      (node (ref "R8") (pin "2") (pinfunction "2_2") (pintype "passive"))
      (node (ref "THRUSTER_CURR_ADC") (pin "10") (pinfunction "REF_10") (pintype "bidirectional"))
      (node (ref "THRUSTER_CURR_ADC") (pin "16") (pinfunction "VDD_16") (pintype "bidirectional"))
      (node (ref "U$11") (pin "P$8") (pinfunction "VCC_P$8") (pintype "bidirectional"))
      (node (ref "U$14") (pin "P$8") (pinfunction "VCC_P$8") (pintype "bidirectional"))
      (node (ref "U$17") (pin "P$8") (pinfunction "VCC_P$8") (pintype "bidirectional"))
      (node (ref "U$19") (pin "P$8") (pinfunction "VCC_P$8") (pintype "bidirectional"))
      (node (ref "U$20") (pin "P$2") (pinfunction "P$2_P$2") (pintype "bidirectional"))
      (node (ref "U$23") (pin "P$8") (pinfunction "VCC_P$8") (pintype "bidirectional"))
      (node (ref "U$29") (pin "P$8") (pinfunction "VCC_P$8") (pintype "bidirectional"))
      (node (ref "U$3") (pin "3-1") (pinfunction "5V_3-1") (pintype "bidirectional"))
      (node (ref "U$35") (pin "P$8") (pinfunction "VCC_P$8") (pintype "bidirectional"))
      (node (ref "U$39") (pin "P$8") (pinfunction "VCC_P$8") (pintype "bidirectional"))
      (node (ref "U$4") (pin "P$8") (pinfunction "VCC_P$8") (pintype "bidirectional"))
      (node (ref "U$45") (pin "P$5") (pinfunction "VDD_P$5") (pintype "bidirectional"))
      (node (ref "U$51") (pin "P$2") (pinfunction "C_P$2") (pintype "passive"))
      (node (ref "U$52") (pin "P$2") (pinfunction "C_P$2") (pintype "passive"))
      (node (ref "U$53") (pin "P$2") (pinfunction "C_P$2") (pintype "passive"))
      (node (ref "U$54") (pin "P$2") (pinfunction "C_P$2") (pintype "passive"))
      (node (ref "U$64") (pin "P$2") (pinfunction "C_P$2") (pintype "passive"))
      (node (ref "U$65") (pin "P$2") (pinfunction "C_P$2") (pintype "passive"))
      (node (ref "U$8") (pin "P$8") (pinfunction "VCC_P$8") (pintype "bidirectional"))
      (node (ref "U1") (pin "1") (pinfunction "A0_1") (pintype "bidirectional"))
      (node (ref "U1") (pin "2") (pinfunction "A1_2") (pintype "bidirectional"))
      (node (ref "U1") (pin "24") (pinfunction "A5_24") (pintype "bidirectional"))
      (node (ref "U1") (pin "28") (pinfunction "VDD_28") (pintype "bidirectional"))
      (node (ref "U1") (pin "3") (pinfunction "A2_3") (pintype "bidirectional"))
      (node (ref "U1") (pin "4") (pinfunction "A3_4") (pintype "bidirectional"))
      (node (ref "U1") (pin "5") (pinfunction "A4_5") (pintype "bidirectional"))
      (node (ref "V-THRUST_CURR_ADC") (pin "P$3") (pinfunction "ADR0_P$3") (pintype "bidirectional"))
      (node (ref "V-THRUST_CURR_ADC") (pin "P$5") (pinfunction "VDD_P$5") (pintype "bidirectional"))
      (node (ref "V-THRUST_CURR_ADC") (pin "P$6") (pinfunction "ADR1_P$6") (pintype "bidirectional"))
      (node (ref "V-THRUST_VOLAGE") (pin "P$4") (pinfunction "VS_P$4") (pintype "bidirectional"))
      (node (ref "V-THRUST_VOLAGE") (pin "P$7") (pinfunction "A0_P$7") (pintype "bidirectional"))
      (node (ref "V-THRUST_VOLAGE") (pin "P$8") (pinfunction "A1_P$8") (pintype "bidirectional"))
    )
    (net (code "4") (name "/5V_PG") (class "Default")
      (node (ref "FAULT2") (pin "2") (pinfunction "2_2") (pintype "passive"))
    )
    (net (code "5") (name "/12V") (class "Default")
      (node (ref "12V_OUT") (pin "P$1") (pinfunction "P$1_P$1") (pintype "bidirectional"))
      (node (ref "C44") (pin "1") (pinfunction "1_1") (pintype "passive"))
      (node (ref "C45") (pin "1") (pinfunction "1_1") (pintype "passive"))
      (node (ref "C50") (pin "1") (pinfunction "1_1") (pintype "passive"))
      (node (ref "CPU_PWR") (pin "P$3") (pinfunction "P$3_P$3") (pintype "bidirectional"))
      (node (ref "CPU_PWR") (pin "P$4") (pinfunction "P$4_P$4") (pintype "bidirectional"))
      (node (ref "R25") (pin "1") (pinfunction "1_1") (pintype "passive"))
      (node (ref "R33") (pin "2") (pinfunction "2_2") (pintype "passive"))
      (node (ref "U$36") (pin "P$2") (pinfunction "P$2_P$2") (pintype "bidirectional"))
      (node (ref "U$46") (pin "P$1") (pinfunction "C_P$1") (pintype "passive"))
      (node (ref "U$47") (pin "P$1") (pinfunction "C_P$1") (pintype "passive"))
      (node (ref "U$48") (pin "P$1") (pinfunction "C_P$1") (pintype "passive"))
      (node (ref "U$49") (pin "P$1") (pinfunction "C_P$1") (pintype "passive"))
    )
    (net (code "6") (name "/AIN0") (class "Default")
      (node (ref "U$3") (pin "3-9") (pinfunction "PE3_3-9") (pintype "bidirectional"))
    )
    (net (code "7") (name "/AIN1") (class "Default")
      (node (ref "U$3") (pin "3-8") (pinfunction "PE2_3-8") (pintype "bidirectional"))
    )
    (net (code "8") (name "/AIN2") (class "Default")
      (node (ref "U$3") (pin "3-7") (pinfunction "PE1_3-7") (pintype "bidirectional"))
    )
    (net (code "9") (name "/AIN3") (class "Default")
      (node (ref "U$3") (pin "2-3") (pinfunction "PE0_2-3") (pintype "bidirectional"))
    )
    (net (code "10") (name "/AIN4") (class "Default")
      (node (ref "U$3") (pin "3-6") (pinfunction "PD3_3-6") (pintype "bidirectional"))
    )
    (net (code "11") (name "/AIN5") (class "Default")
      (node (ref "U$3") (pin "3-5") (pinfunction "PD2_3-5") (pintype "bidirectional"))
    )
    (net (code "12") (name "/AIN8") (class "Default")
      (node (ref "U$3") (pin "1-6") (pinfunction "PE5_1-6") (pintype "bidirectional"))
    )
    (net (code "13") (name "/AIN9") (class "Default")
      (node (ref "U$3") (pin "1-5") (pinfunction "PE4_1-5") (pintype "bidirectional"))
    )
    (net (code "14") (name "/AIN10") (class "Default")
      (node (ref "U$3") (pin "1-7") (pinfunction "PB4_1-7") (pintype "bidirectional"))
    )
    (net (code "15") (name "/AIN11") (class "Default")
      (node (ref "U$3") (pin "1-2") (pinfunction "PB5_1-2") (pintype "bidirectional"))
    )
    (net (code "16") (name "/CPU_ON") (class "Default")
      (node (ref "12V_REG") (pin "14") (pinfunction "EN/UV_14") (pintype "bidirectional"))
      (node (ref "U$45") (pin "P$4") (pinfunction "OUT_P$4") (pintype "bidirectional"))
    )
    (net (code "17") (name "/RELAY-SHORE") (class "Default")
      (node (ref "R39") (pin "2") (pinfunction "2_2") (pintype "passive"))
      (node (ref "SHORE-FET") (pin "3") (pinfunction "S_3") (pintype "passive"))
      (node (ref "U$25") (pin "2A") (pinfunction "2_2A") (pintype "bidirectional"))
      (node (ref "U$25") (pin "2B") (pinfunction "2_2B") (pintype "bidirectional"))
    )
    (net (code "18") (name "/RELAY_OUT") (class "Default")
      (node (ref "12V_REG") (pin "13") (pinfunction "VIN-2_13") (pintype "bidirectional"))
      (node (ref "12V_REG") (pin "4") (pinfunction "VIN-1_4") (pintype "bidirectional"))
      (node (ref "5V_REG") (pin "13") (pinfunction "VIN-2_13") (pintype "bidirectional"))
      (node (ref "5V_REG") (pin "14") (pinfunction "EN/UV_14") (pintype "bidirectional"))
      (node (ref "5V_REG") (pin "4") (pinfunction "VIN-1_4") (pintype "bidirectional"))
      (node (ref "C27") (pin "1") (pinfunction "1_1") (pintype "passive"))
      (node (ref "C34") (pin "1") (pinfunction "1_1") (pintype "passive"))
      (node (ref "C38") (pin "1") (pinfunction "1_1") (pintype "passive"))
      (node (ref "C4") (pin "1") (pinfunction "1_1") (pintype "passive"))
      (node (ref "C40") (pin "1") (pinfunction "1_1") (pintype "passive"))
      (node (ref "C59") (pin "+") (pinfunction "+_+") (pintype "passive"))
      (node (ref "C60") (pin "1") (pinfunction "1_1") (pintype "passive"))
      (node (ref "R20") (pin "2") (pinfunction "2_2") (pintype "passive"))
      (node (ref "R3") (pin "2") (pinfunction "2_2") (pintype "passive"))
      (node (ref "R40") (pin "2") (pinfunction "2_2") (pintype "passive"))
      (node (ref "U$1") (pin "P$1") (pinfunction "S_P$1") (pintype "bidirectional"))
      (node (ref "U$19") (pin "P$1") (pinfunction "IP+_P$1") (pintype "bidirectional"))
      (node (ref "U$19") (pin "P$2") (pinfunction "IP+_P$2") (pintype "bidirectional"))
      (node (ref "U$25") (pin "7A") (pinfunction "7_7A") (pintype "bidirectional"))
      (node (ref "U$25") (pin "7B") (pinfunction "7_7B") (pintype "bidirectional"))
      (node (ref "U$50") (pin "P$2") (pinfunction "C_P$2") (pintype "passive"))
      (node (ref "U$66") (pin "P$1") (pinfunction "S_P$1") (pintype "bidirectional"))
    )
    (net (code "19") (name "/RX") (class "Default")
      (node (ref "U$3") (pin "1-3") (pinfunction "PB0_1-3") (pintype "bidirectional"))
    )
    (net (code "20") (name "/SCL-3V3") (class "Default")
      (node (ref "BME280") (pin "P$4") (pinfunction "SCK/SCL_P$4") (pintype "bidirectional"))
      (node (ref "DEPTH_SENS") (pin "P$1") (pinfunction "P$1_P$1") (pintype "bidirectional"))
      (node (ref "I2C_SHIFT") (pin "P$3") (pinfunction "SCL1_P$3") (pintype "bidirectional"))
      (node (ref "R11") (pin "1") (pinfunction "1_1") (pintype "passive"))
    )
    (net (code "21") (name "/SCL1") (class "Default")
      (node (ref "12V_CURR_ADC") (pin "P$1") (pinfunction "SCL_P$1") (pintype "bidirectional"))
      (node (ref "12V_VOLTAGE") (pin "P$5") (pinfunction "SCL_P$5") (pintype "bidirectional"))
      (node (ref "5V_CURR_ADC") (pin "P$1") (pinfunction "SCL_P$1") (pintype "bidirectional"))
      (node (ref "5V_VOLTAGE") (pin "P$5") (pinfunction "SCL_P$5") (pintype "bidirectional"))
      (node (ref "I2C_SHIFT") (pin "P$6") (pinfunction "SCL2_P$6") (pintype "bidirectional"))
      (node (ref "R8") (pin "1") (pinfunction "1_1") (pintype "passive"))
      (node (ref "THRUSTER_CURR_ADC") (pin "14") (pinfunction "SCL_14") (pintype "bidirectional"))
      (node (ref "U$3") (pin "1-9") (pinfunction "PA6_1-9") (pintype "bidirectional"))
      (node (ref "U1") (pin "26") (pinfunction "SCL_26") (pintype "bidirectional"))
      (node (ref "V-THRUST_CURR_ADC") (pin "P$1") (pinfunction "SCL_P$1") (pintype "bidirectional"))
      (node (ref "V-THRUST_VOLAGE") (pin "P$5") (pinfunction "SCL_P$5") (pintype "bidirectional"))
    )
    (net (code "22") (name "/SCL3") (class "Default")
      (node (ref "U$3") (pin "2-7") (pinfunction "PD0_2-7") (pintype "bidirectional"))
    )
    (net (code "23") (name "/SDA-3V3") (class "Default")
      (node (ref "BME280") (pin "P$3") (pinfunction "SDI/SDA_P$3") (pintype "bidirectional"))
      (node (ref "DEPTH_SENS") (pin "P$2") (pinfunction "P$2_P$2") (pintype "bidirectional"))
      (node (ref "I2C_SHIFT") (pin "P$4") (pinfunction "SDA1_P$4") (pintype "bidirectional"))
      (node (ref "R10") (pin "1") (pinfunction "1_1") (pintype "passive"))
    )
    (net (code "24") (name "/SDA1") (class "Default")
      (node (ref "12V_CURR_ADC") (pin "P$8") (pinfunction "SDA_P$8") (pintype "bidirectional"))
      (node (ref "12V_VOLTAGE") (pin "P$6") (pinfunction "SDA_P$6") (pintype "bidirectional"))
      (node (ref "5V_CURR_ADC") (pin "P$8") (pinfunction "SDA_P$8") (pintype "bidirectional"))
      (node (ref "5V_VOLTAGE") (pin "P$6") (pinfunction "SDA_P$6") (pintype "bidirectional"))
      (node (ref "I2C_SHIFT") (pin "P$5") (pinfunction "SDA2_P$5") (pintype "bidirectional"))
      (node (ref "R7") (pin "1") (pinfunction "1_1") (pintype "passive"))
      (node (ref "THRUSTER_CURR_ADC") (pin "15") (pinfunction "SDA_15") (pintype "bidirectional"))
      (node (ref "U$3") (pin "1-10") (pinfunction "PA7_1-10") (pintype "bidirectional"))
      (node (ref "U1") (pin "27") (pinfunction "SDA_27") (pintype "bidirectional"))
      (node (ref "V-THRUST_CURR_ADC") (pin "P$8") (pinfunction "SDA_P$8") (pintype "bidirectional"))
      (node (ref "V-THRUST_VOLAGE") (pin "P$6") (pinfunction "SDA_P$6") (pintype "bidirectional"))
    )
    (net (code "25") (name "/SDA3") (class "Default")
      (node (ref "U$3") (pin "2-6") (pinfunction "PD1_2-6") (pintype "bidirectional"))
    )
    (net (code "26") (name "/T1_CURR") (class "Default")
      (node (ref "THRUSTER_CURR_ADC") (pin "1") (pinfunction "CH0_1") (pintype "bidirectional"))
      (node (ref "U$4") (pin "P$7") (pinfunction "VIOUT_P$7") (pintype "bidirectional"))
    )
    (net (code "27") (name "/T1_PWM") (class "Default")
      (node (ref "THRUST1") (pin "P$2") (pinfunction "P$2_P$2") (pintype "bidirectional"))
      (node (ref "U1") (pin "6") (pinfunction "CH0_6") (pintype "bidirectional"))
    )
    (net (code "28") (name "/T2_CURR") (class "Default")
      (node (ref "THRUSTER_CURR_ADC") (pin "2") (pinfunction "CH1_2") (pintype "bidirectional"))
      (node (ref "U$8") (pin "P$7") (pinfunction "VIOUT_P$7") (pintype "bidirectional"))
    )
    (net (code "29") (name "/T2_PWM") (class "Default")
      (node (ref "THRUST2") (pin "P$2") (pinfunction "P$2_P$2") (pintype "bidirectional"))
      (node (ref "U1") (pin "7") (pinfunction "CH1_7") (pintype "bidirectional"))
    )
    (net (code "30") (name "/T3_CURR") (class "Default")
      (node (ref "THRUSTER_CURR_ADC") (pin "3") (pinfunction "CH2_3") (pintype "bidirectional"))
      (node (ref "U$11") (pin "P$7") (pinfunction "VIOUT_P$7") (pintype "bidirectional"))
    )
    (net (code "31") (name "/T3_PWM") (class "Default")
      (node (ref "THRUST3") (pin "P$2") (pinfunction "P$2_P$2") (pintype "bidirectional"))
      (node (ref "U1") (pin "8") (pinfunction "CH2_8") (pintype "bidirectional"))
    )
    (net (code "32") (name "/T4_CURR") (class "Default")
      (node (ref "THRUSTER_CURR_ADC") (pin "4") (pinfunction "CH3_4") (pintype "bidirectional"))
      (node (ref "U$14") (pin "P$7") (pinfunction "VIOUT_P$7") (pintype "bidirectional"))
    )
    (net (code "33") (name "/T4_PWM") (class "Default")
      (node (ref "THRUST4") (pin "P$2") (pinfunction "P$2_P$2") (pintype "bidirectional"))
      (node (ref "U1") (pin "9") (pinfunction "CH3_9") (pintype "bidirectional"))
    )
    (net (code "34") (name "/T5_CURR") (class "Default")
      (node (ref "THRUSTER_CURR_ADC") (pin "5") (pinfunction "CH4_5") (pintype "bidirectional"))
      (node (ref "U$17") (pin "P$7") (pinfunction "VIOUT_P$7") (pintype "bidirectional"))
    )
    (net (code "35") (name "/T5_PWM") (class "Default")
      (node (ref "THRUST5") (pin "P$2") (pinfunction "P$2_P$2") (pintype "bidirectional"))
      (node (ref "U1") (pin "10") (pinfunction "CH4_10") (pintype "bidirectional"))
    )
    (net (code "36") (name "/T6_CURR") (class "Default")
      (node (ref "THRUSTER_CURR_ADC") (pin "6") (pinfunction "CH5_6") (pintype "bidirectional"))
      (node (ref "U$23") (pin "P$7") (pinfunction "VIOUT_P$7") (pintype "bidirectional"))
    )
    (net (code "37") (name "/T6_PWM") (class "Default")
      (node (ref "THRUST6") (pin "P$2") (pinfunction "P$2_P$2") (pintype "bidirectional"))
      (node (ref "U1") (pin "11") (pinfunction "CH5_11") (pintype "bidirectional"))
    )
    (net (code "38") (name "/T7_CURR") (class "Default")
      (node (ref "THRUSTER_CURR_ADC") (pin "7") (pinfunction "CH6_7") (pintype "bidirectional"))
      (node (ref "U$29") (pin "P$7") (pinfunction "VIOUT_P$7") (pintype "bidirectional"))
    )
    (net (code "39") (name "/T7_PWM") (class "Default")
      (node (ref "THRUST7") (pin "P$2") (pinfunction "P$2_P$2") (pintype "bidirectional"))
      (node (ref "U1") (pin "12") (pinfunction "CH6_12") (pintype "bidirectional"))
    )
    (net (code "40") (name "/T8_CURR") (class "Default")
      (node (ref "THRUSTER_CURR_ADC") (pin "8") (pinfunction "CH7_8") (pintype "bidirectional"))
      (node (ref "U$39") (pin "P$7") (pinfunction "VIOUT_P$7") (pintype "bidirectional"))
    )
    (net (code "41") (name "/T8_PWM") (class "Default")
      (node (ref "THRUST8") (pin "P$2") (pinfunction "P$2_P$2") (pintype "bidirectional"))
      (node (ref "U1") (pin "13") (pinfunction "CH7_13") (pintype "bidirectional"))
    )
    (net (code "42") (name "/TX") (class "Default")
      (node (ref "U$3") (pin "1-4") (pinfunction "PB1_1-4") (pintype "bidirectional"))
    )
    (net (code "43") (name "/V_THRUST") (class "Default")
      (node (ref "C46") (pin "1") (pinfunction "1_1") (pintype "passive"))
      (node (ref "C47") (pin "1") (pinfunction "1_1") (pintype "passive"))
      (node (ref "C49") (pin "1") (pinfunction "1_1") (pintype "passive"))
      (node (ref "CAMERA1") (pin "P$1") (pinfunction "P$1_P$1") (pintype "bidirectional"))
      (node (ref "CAMERA2") (pin "P$1") (pinfunction "P$1_P$1") (pintype "bidirectional"))
      (node (ref "R30") (pin "1") (pinfunction "1_1") (pintype "passive"))
      (node (ref "R32") (pin "2") (pinfunction "2_2") (pintype "passive"))
      (node (ref "U$11") (pin "P$1") (pinfunction "IP+_P$1") (pintype "bidirectional"))
      (node (ref "U$11") (pin "P$2") (pinfunction "IP+_P$2") (pintype "bidirectional"))
      (node (ref "U$14") (pin "P$1") (pinfunction "IP+_P$1") (pintype "bidirectional"))
      (node (ref "U$14") (pin "P$2") (pinfunction "IP+_P$2") (pintype "bidirectional"))
      (node (ref "U$17") (pin "P$1") (pinfunction "IP+_P$1") (pintype "bidirectional"))
      (node (ref "U$17") (pin "P$2") (pinfunction "IP+_P$2") (pintype "bidirectional"))
      (node (ref "U$23") (pin "P$1") (pinfunction "IP+_P$1") (pintype "bidirectional"))
      (node (ref "U$23") (pin "P$2") (pinfunction "IP+_P$2") (pintype "bidirectional"))
      (node (ref "U$29") (pin "P$1") (pinfunction "IP+_P$1") (pintype "bidirectional"))
      (node (ref "U$29") (pin "P$2") (pinfunction "IP+_P$2") (pintype "bidirectional"))
      (node (ref "U$32") (pin "P$2") (pinfunction "C_P$2") (pintype "passive"))
      (node (ref "U$33") (pin "P$2") (pinfunction "C_P$2") (pintype "passive"))
      (node (ref "U$34") (pin "P$2") (pinfunction "C_P$2") (pintype "passive"))
      (node (ref "U$38") (pin "P$2") (pinfunction "C_P$2") (pintype "passive"))
      (node (ref "U$39") (pin "P$1") (pinfunction "IP+_P$1") (pintype "bidirectional"))
      (node (ref "U$39") (pin "P$2") (pinfunction "IP+_P$2") (pintype "bidirectional"))
      (node (ref "U$4") (pin "P$1") (pinfunction "IP+_P$1") (pintype "bidirectional"))
      (node (ref "U$4") (pin "P$2") (pinfunction "IP+_P$2") (pintype "bidirectional"))
      (node (ref "U$5") (pin "P$3") (pinfunction "P$2_P$3") (pintype "bidirectional"))
      (node (ref "U$5") (pin "P$4") (pinfunction "P$2_P$4") (pintype "bidirectional"))
      (node (ref "U$8") (pin "P$1") (pinfunction "IP+_P$1") (pintype "bidirectional"))
      (node (ref "U$8") (pin "P$2") (pinfunction "IP+_P$2") (pintype "bidirectional"))
      (node (ref "V-THRUST_OUT") (pin "P$1") (pinfunction "P$1_P$1") (pintype "bidirectional"))
    )
    (net (code "44") (name "FAULT") (class "Default")
      (node (ref "IC1") (pin "4") (pinfunction "O_4") (pintype "output"))
      (node (ref "IC3") (pin "2") (pinfunction "I1_2") (pintype "input"))
      (node (ref "IC4") (pin "4") (pinfunction "O_4") (pintype "output"))
      (node (ref "OFF") (pin "3") (pinfunction "3_3") (pintype "passive"))
      (node (ref "OFF") (pin "4") (pinfunction "4_4") (pintype "passive"))
      (node (ref "OFF_SW") (pin "1") (pinfunction "1_1") (pintype "passive"))
    )
    (net (code "45") (name "FET") (class "Default")
      (node (ref "IC3") (pin "4") (pinfunction "O_4") (pintype "output"))
      (node (ref "N1") (pin "1") (pinfunction "G_1") (pintype "passive"))
      (node (ref "R53") (pin "2") (pinfunction "2_2") (pintype "passive"))
    )
    (net (code "46") (name "GND") (class "Default")
      (node (ref "12V_CURR_ADC") (pin "P$3") (pinfunction "ADR0_P$3") (pintype "bidirectional"))
      (node (ref "12V_CURR_ADC") (pin "P$6") (pinfunction "ADR1_P$6") (pintype "bidirectional"))
      (node (ref "12V_CURR_ADC") (pin "P$7") (pinfunction "GND_P$7") (pintype "bidirectional"))
      (node (ref "12V_LED") (pin "P$2") (pinfunction "C_P$2") (pintype "passive"))
      (node (ref "12V_OUT") (pin "P$2") (pinfunction "P$2_P$2") (pintype "bidirectional"))
      (node (ref "12V_REG") (pin "10") (pinfunction "GND-2_10") (pintype "bidirectional"))
      (node (ref "12V_REG") (pin "11") (pinfunction "GND-2_11") (pintype "bidirectional"))
      (node (ref "12V_REG") (pin "18") (pinfunction "GND_18") (pintype "bidirectional"))
      (node (ref "12V_REG") (pin "6") (pinfunction "GND-1_6") (pintype "bidirectional"))
      (node (ref "12V_REG") (pin "7") (pinfunction "GND-1_7") (pintype "bidirectional"))
      (node (ref "12V_VOLTAGE") (pin "P$3") (pinfunction "GND_P$3") (pintype "bidirectional"))
      (node (ref "12V_VOLTAGE") (pin "P$7") (pinfunction "A0_P$7") (pintype "bidirectional"))
      (node (ref "3V3_LED") (pin "P$2") (pinfunction "C_P$2") (pintype "passive"))
      (node (ref "5V_CURR_ADC") (pin "P$3") (pinfunction "ADR0_P$3") (pintype "bidirectional"))
      (node (ref "5V_CURR_ADC") (pin "P$7") (pinfunction "GND_P$7") (pintype "bidirectional"))
      (node (ref "5V_LED") (pin "P$2") (pinfunction "C_P$2") (pintype "passive"))
      (node (ref "5V_OUT") (pin "P$2") (pinfunction "P$2_P$2") (pintype "bidirectional"))
      (node (ref "5V_PG") (pin "C") (pinfunction "C_C") (pintype "passive"))
      (node (ref "5V_REG") (pin "10") (pinfunction "GND-2_10") (pintype "bidirectional"))
      (node (ref "5V_REG") (pin "11") (pinfunction "GND-2_11") (pintype "bidirectional"))
      (node (ref "5V_REG") (pin "18") (pinfunction "GND_18") (pintype "bidirectional"))
      (node (ref "5V_REG") (pin "6") (pinfunction "GND-1_6") (pintype "bidirectional"))
      (node (ref "5V_REG") (pin "7") (pinfunction "GND-1_7") (pintype "bidirectional"))
      (node (ref "5V_VOLTAGE") (pin "P$3") (pinfunction "GND_P$3") (pintype "bidirectional"))
      (node (ref "5V_VOLTAGE") (pin "P$7") (pinfunction "A0_P$7") (pintype "bidirectional"))
      (node (ref "5V_VOLTAGE") (pin "P$8") (pinfunction "A1_P$8") (pintype "bidirectional"))
      (node (ref "BATTERY_IN") (pin "P$2") (pinfunction "P$2_P$2") (pintype "bidirectional"))
      (node (ref "BATTERY_LED") (pin "P$2") (pinfunction "C_P$2") (pintype "passive"))
      (node (ref "BME280") (pin "P$1") (pinfunction "GND1_P$1") (pintype "bidirectional"))
      (node (ref "BME280") (pin "P$7") (pinfunction "GND2_P$7") (pintype "bidirectional"))
      (node (ref "C1") (pin "2") (pinfunction "2_2") (pintype "passive"))
      (node (ref "C10") (pin "2") (pinfunction "2_2") (pintype "passive"))
      (node (ref "C11") (pin "2") (pinfunction "2_2") (pintype "passive"))
      (node (ref "C12") (pin "2") (pinfunction "2_2") (pintype "passive"))
      (node (ref "C13") (pin "2") (pinfunction "2_2") (pintype "passive"))
      (node (ref "C14") (pin "2") (pinfunction "2_2") (pintype "passive"))
      (node (ref "C15") (pin "2") (pinfunction "2_2") (pintype "passive"))
      (node (ref "C16") (pin "2") (pinfunction "2_2") (pintype "passive"))
      (node (ref "C17") (pin "2") (pinfunction "2_2") (pintype "passive"))
      (node (ref "C18") (pin "2") (pinfunction "2_2") (pintype "passive"))
      (node (ref "C19") (pin "2") (pinfunction "2_2") (pintype "passive"))
      (node (ref "C2") (pin "2") (pinfunction "2_2") (pintype "passive"))
      (node (ref "C20") (pin "2") (pinfunction "2_2") (pintype "passive"))
      (node (ref "C21") (pin "2") (pinfunction "2_2") (pintype "passive"))
      (node (ref "C22") (pin "2") (pinfunction "2_2") (pintype "passive"))
      (node (ref "C23") (pin "2") (pinfunction "2_2") (pintype "passive"))
      (node (ref "C24") (pin "2") (pinfunction "2_2") (pintype "passive"))
      (node (ref "C25") (pin "2") (pinfunction "2_2") (pintype "passive"))
      (node (ref "C26") (pin "2") (pinfunction "2_2") (pintype "passive"))
      (node (ref "C27") (pin "2") (pinfunction "2_2") (pintype "passive"))
      (node (ref "C29") (pin "2") (pinfunction "2_2") (pintype "passive"))
      (node (ref "C3") (pin "2") (pinfunction "2_2") (pintype "passive"))
      (node (ref "C30") (pin "2") (pinfunction "2_2") (pintype "passive"))
      (node (ref "C31") (pin "2") (pinfunction "2_2") (pintype "passive"))
      (node (ref "C33") (pin "2") (pinfunction "2_2") (pintype "passive"))
      (node (ref "C34") (pin "2") (pinfunction "2_2") (pintype "passive"))
      (node (ref "C35") (pin "2") (pinfunction "2_2") (pintype "passive"))
      (node (ref "C36") (pin "P$2") (pinfunction "-_P$2") (pintype "passive"))
      (node (ref "C37") (pin "2") (pinfunction "2_2") (pintype "passive"))
      (node (ref "C38") (pin "2") (pinfunction "2_2") (pintype "passive"))
      (node (ref "C39") (pin "2") (pinfunction "2_2") (pintype "passive"))
      (node (ref "C4") (pin "2") (pinfunction "2_2") (pintype "passive"))
      (node (ref "C40") (pin "2") (pinfunction "2_2") (pintype "passive"))
      (node (ref "C43") (pin "2") (pinfunction "2_2") (pintype "passive"))
      (node (ref "C44") (pin "2") (pinfunction "2_2") (pintype "passive"))
      (node (ref "C45") (pin "2") (pinfunction "2_2") (pintype "passive"))
      (node (ref "C46") (pin "2") (pinfunction "2_2") (pintype "passive"))
      (node (ref "C47") (pin "2") (pinfunction "2_2") (pintype "passive"))
      (node (ref "C48") (pin "2") (pinfunction "2_2") (pintype "passive"))
      (node (ref "C49") (pin "2") (pinfunction "2_2") (pintype "passive"))
      (node (ref "C5") (pin "2") (pinfunction "2_2") (pintype "passive"))
      (node (ref "C50") (pin "2") (pinfunction "2_2") (pintype "passive"))
      (node (ref "C51") (pin "2") (pinfunction "2_2") (pintype "passive"))
      (node (ref "C52") (pin "2") (pinfunction "2_2") (pintype "passive"))
      (node (ref "C53") (pin "2") (pinfunction "2_2") (pintype "passive"))
      (node (ref "C54") (pin "2") (pinfunction "2_2") (pintype "passive"))
      (node (ref "C55") (pin "2") (pinfunction "2_2") (pintype "passive"))
      (node (ref "C56") (pin "2") (pinfunction "2_2") (pintype "passive"))
      (node (ref "C57") (pin "2") (pinfunction "2_2") (pintype "passive"))
      (node (ref "C58") (pin "2") (pinfunction "2_2") (pintype "passive"))
      (node (ref "C59") (pin "-") (pinfunction "-_-") (pintype "passive"))
      (node (ref "C6") (pin "2") (pinfunction "2_2") (pintype "passive"))
      (node (ref "C60") (pin "2") (pinfunction "2_2") (pintype "passive"))
      (node (ref "C61") (pin "2") (pinfunction "2_2") (pintype "passive"))
      (node (ref "C62") (pin "P$2") (pinfunction "-_P$2") (pintype "passive"))
      (node (ref "C63") (pin "2") (pinfunction "2_2") (pintype "passive"))
      (node (ref "C64") (pin "2") (pinfunction "2_2") (pintype "passive"))
      (node (ref "C66") (pin "2") (pinfunction "2_2") (pintype "passive"))
      (node (ref "C67") (pin "2") (pinfunction "2_2") (pintype "passive"))
      (node (ref "C68") (pin "2") (pinfunction "2_2") (pintype "passive"))
      (node (ref "C69") (pin "2") (pinfunction "2_2") (pintype "passive"))
      (node (ref "C7") (pin "2") (pinfunction "2_2") (pintype "passive"))
      (node (ref "C70") (pin "2") (pinfunction "2_2") (pintype "passive"))
      (node (ref "C71") (pin "2") (pinfunction "2_2") (pintype "passive"))
      (node (ref "C72") (pin "-") (pinfunction "-_-") (pintype "passive"))
      (node (ref "C73") (pin "2") (pinfunction "2_2") (pintype "passive"))
      (node (ref "C74") (pin "2") (pinfunction "2_2") (pintype "passive"))
      (node (ref "C75") (pin "2") (pinfunction "2_2") (pintype "passive"))
      (node (ref "C76") (pin "-") (pinfunction "-_-") (pintype "passive"))
      (node (ref "C8") (pin "2") (pinfunction "2_2") (pintype "passive"))
      (node (ref "C9") (pin "2") (pinfunction "2_2") (pintype "passive"))
      (node (ref "CAMERA1") (pin "P$2") (pinfunction "P$2_P$2") (pintype "bidirectional"))
      (node (ref "CAMERA2") (pin "P$2") (pinfunction "P$2_P$2") (pintype "bidirectional"))
      (node (ref "CPU_PWR") (pin "P$1") (pinfunction "P$1_P$1") (pintype "bidirectional"))
      (node (ref "CPU_PWR") (pin "P$2") (pinfunction "P$2_P$2") (pintype "bidirectional"))
      (node (ref "DEPTH_SENS") (pin "P$3") (pinfunction "P$3_P$3") (pintype "bidirectional"))
      (node (ref "ETHERNET") (pin "P$2") (pinfunction "P$2_P$2") (pintype "bidirectional"))
      (node (ref "FAN1") (pin "P$2") (pinfunction "P$2_P$2") (pintype "bidirectional"))
      (node (ref "FAN2") (pin "P$2") (pinfunction "P$2_P$2") (pintype "bidirectional"))
      (node (ref "I2C_SHIFT") (pin "P$1") (pinfunction "GND_P$1") (pintype "bidirectional"))
      (node (ref "IC2") (pin "4") (pinfunction "GND_4") (pintype "power_in"))
      (node (ref "IC3") (pin "3") (pinfunction "GND_3") (pintype "power_in"))
      (node (ref "LED2") (pin "C") (pinfunction "C_C") (pintype "passive"))
      (node (ref "N1") (pin "2") (pinfunction "S_2") (pintype "passive"))
      (node (ref "OFF") (pin "1") (pinfunction "1_1") (pintype "passive"))
      (node (ref "OFF") (pin "2") (pinfunction "2_2") (pintype "passive"))
      (node (ref "OFF_SW") (pin "2") (pinfunction "2_2") (pintype "passive"))
      (node (ref "ON") (pin "1") (pinfunction "1_1") (pintype "passive"))
      (node (ref "ON") (pin "2") (pinfunction "2_2") (pintype "passive"))
      (node (ref "ON_INDICATOR") (pin "C") (pinfunction "C_C") (pintype "passive"))
      (node (ref "ON_SW") (pin "2") (pinfunction "2_2") (pintype "passive"))
      (node (ref "R14") (pin "1") (pinfunction "1_1") (pintype "passive"))
      (node (ref "R16") (pin "1") (pinfunction "1_1") (pintype "passive"))
      (node (ref "R17") (pin "1") (pinfunction "1_1") (pintype "passive"))
      (node (ref "R19") (pin "2") (pinfunction "2_2") (pintype "passive"))
      (node (ref "R22") (pin "2") (pinfunction "2_2") (pintype "passive"))
      (node (ref "R24") (pin "1") (pinfunction "1_1") (pintype "passive"))
      (node (ref "R44") (pin "1") (pinfunction "1_1") (pintype "passive"))
      (node (ref "R46") (pin "1") (pinfunction "1_1") (pintype "passive"))
      (node (ref "R50") (pin "1") (pinfunction "1_1") (pintype "passive"))
      (node (ref "R51") (pin "1") (pinfunction "1_1") (pintype "passive"))
      (node (ref "R53") (pin "1") (pinfunction "1_1") (pintype "passive"))
      (node (ref "R58") (pin "1") (pinfunction "1_1") (pintype "passive"))
      (node (ref "R59") (pin "1") (pinfunction "E_1") (pintype "passive"))
      (node (ref "R60") (pin "1") (pinfunction "1_1") (pintype "passive"))
      (node (ref "RELAY-OUT_LED") (pin "P$2") (pinfunction "C_P$2") (pintype "passive"))
      (node (ref "SHORE_IN") (pin "P$2") (pinfunction "P$2_P$2") (pintype "bidirectional"))
      (node (ref "SHORE_LED") (pin "P$2") (pinfunction "C_P$2") (pintype "passive"))
      (node (ref "THRUST1") (pin "P$1") (pinfunction "P$1_P$1") (pintype "bidirectional"))
      (node (ref "THRUST1") (pin "P$3") (pinfunction "P$3_P$3") (pintype "bidirectional"))
      (node (ref "THRUST2") (pin "P$1") (pinfunction "P$1_P$1") (pintype "bidirectional"))
      (node (ref "THRUST2") (pin "P$3") (pinfunction "P$3_P$3") (pintype "bidirectional"))
      (node (ref "THRUST3") (pin "P$1") (pinfunction "P$1_P$1") (pintype "bidirectional"))
      (node (ref "THRUST3") (pin "P$3") (pinfunction "P$3_P$3") (pintype "bidirectional"))
      (node (ref "THRUST4") (pin "P$1") (pinfunction "P$1_P$1") (pintype "bidirectional"))
      (node (ref "THRUST4") (pin "P$3") (pinfunction "P$3_P$3") (pintype "bidirectional"))
      (node (ref "THRUST5") (pin "P$1") (pinfunction "P$1_P$1") (pintype "bidirectional"))
      (node (ref "THRUST5") (pin "P$3") (pinfunction "P$3_P$3") (pintype "bidirectional"))
      (node (ref "THRUST6") (pin "P$1") (pinfunction "P$1_P$1") (pintype "bidirectional"))
      (node (ref "THRUST6") (pin "P$3") (pinfunction "P$3_P$3") (pintype "bidirectional"))
      (node (ref "THRUST7") (pin "P$1") (pinfunction "P$1_P$1") (pintype "bidirectional"))
      (node (ref "THRUST7") (pin "P$3") (pinfunction "P$3_P$3") (pintype "bidirectional"))
      (node (ref "THRUST8") (pin "P$1") (pinfunction "P$1_P$1") (pintype "bidirectional"))
      (node (ref "THRUST8") (pin "P$3") (pinfunction "P$3_P$3") (pintype "bidirectional"))
      (node (ref "THRUSTER_CURR_ADC") (pin "12") (pinfunction "A0_12") (pintype "bidirectional"))
      (node (ref "THRUSTER_CURR_ADC") (pin "13") (pinfunction "A1_13") (pintype "bidirectional"))
      (node (ref "THRUSTER_CURR_ADC") (pin "9") (pinfunction "GND_9") (pintype "bidirectional"))
      (node (ref "U$10") (pin "P$1") (pinfunction "A_P$1") (pintype "passive"))
      (node (ref "U$11") (pin "P$5") (pinfunction "GND_P$5") (pintype "bidirectional"))
      (node (ref "U$13") (pin "P$1") (pinfunction "A_P$1") (pintype "passive"))
      (node (ref "U$14") (pin "P$5") (pinfunction "GND_P$5") (pintype "bidirectional"))
      (node (ref "U$16") (pin "P$1") (pinfunction "A_P$1") (pintype "passive"))
      (node (ref "U$17") (pin "P$5") (pinfunction "GND_P$5") (pintype "bidirectional"))
      (node (ref "U$19") (pin "P$5") (pinfunction "GND_P$5") (pintype "bidirectional"))
      (node (ref "U$2") (pin "P$5") (pinfunction "GND_P$5") (pintype "bidirectional"))
      (node (ref "U$22") (pin "P$1") (pinfunction "A_P$1") (pintype "passive"))
      (node (ref "U$23") (pin "P$5") (pinfunction "GND_P$5") (pintype "bidirectional"))
      (node (ref "U$26") (pin "P$1") (pinfunction "A_P$1") (pintype "passive"))
      (node (ref "U$28") (pin "P$1") (pinfunction "A_P$1") (pintype "passive"))
      (node (ref "U$29") (pin "P$5") (pinfunction "GND_P$5") (pintype "bidirectional"))
      (node (ref "U$3") (pin "2-1") (pinfunction "GND_2-1") (pintype "bidirectional"))
      (node (ref "U$3") (pin "3-2") (pinfunction "GND_3-2") (pintype "bidirectional"))
      (node (ref "U$30") (pin "P$1") (pinfunction "A_P$1") (pintype "passive"))
      (node (ref "U$31") (pin "P$1") (pinfunction "A_P$1") (pintype "passive"))
      (node (ref "U$32") (pin "P$1") (pinfunction "A_P$1") (pintype "passive"))
      (node (ref "U$33") (pin "P$1") (pinfunction "A_P$1") (pintype "passive"))
      (node (ref "U$34") (pin "P$1") (pinfunction "A_P$1") (pintype "passive"))
      (node (ref "U$35") (pin "P$5") (pinfunction "GND_P$5") (pintype "bidirectional"))
      (node (ref "U$38") (pin "P$1") (pinfunction "A_P$1") (pintype "passive"))
      (node (ref "U$39") (pin "P$5") (pinfunction "GND_P$5") (pintype "bidirectional"))
      (node (ref "U$4") (pin "P$5") (pinfunction "GND_P$5") (pintype "bidirectional"))
      (node (ref "U$46") (pin "P$2") (pinfunction "A_P$2") (pintype "passive"))
      (node (ref "U$47") (pin "P$2") (pinfunction "A_P$2") (pintype "passive"))
      (node (ref "U$48") (pin "P$2") (pinfunction "A_P$2") (pintype "passive"))
      (node (ref "U$49") (pin "P$2") (pinfunction "A_P$2") (pintype "passive"))
      (node (ref "U$50") (pin "P$1") (pinfunction "A_P$1") (pintype "passive"))
      (node (ref "U$51") (pin "P$1") (pinfunction "A_P$1") (pintype "passive"))
      (node (ref "U$52") (pin "P$1") (pinfunction "A_P$1") (pintype "passive"))
      (node (ref "U$53") (pin "P$1") (pinfunction "A_P$1") (pintype "passive"))
      (node (ref "U$54") (pin "P$1") (pinfunction "A_P$1") (pintype "passive"))
      (node (ref "U$57") (pin "P$1") (pinfunction "A_P$1") (pintype "passive"))
      (node (ref "U$60") (pin "P$1") (pinfunction "A_P$1") (pintype "passive"))
      (node (ref "U$62") (pin "P$1") (pinfunction "P$1_P$1") (pintype "bidirectional"))
      (node (ref "U$63") (pin "P$1") (pinfunction "P$1_P$1") (pintype "bidirectional"))
      (node (ref "U$64") (pin "P$1") (pinfunction "A_P$1") (pintype "passive"))
      (node (ref "U$65") (pin "P$1") (pinfunction "A_P$1") (pintype "passive"))
      (node (ref "U$8") (pin "P$5") (pinfunction "GND_P$5") (pintype "bidirectional"))
      (node (ref "U1") (pin "14") (pinfunction "VSS_14") (pintype "bidirectional"))
      (node (ref "U1") (pin "23") (pinfunction "~{OE}_23") (pintype "bidirectional"))
      (node (ref "U1") (pin "25") (pinfunction "EXTCLK_25") (pintype "bidirectional"))
      (node (ref "U2") (pin "8") (pinfunction "GND_8") (pintype "bidirectional"))
      (node (ref "U3") (pin "8") (pinfunction "GND_8") (pintype "bidirectional"))
      (node (ref "V-THRUST_CURR_ADC") (pin "P$7") (pinfunction "GND_P$7") (pintype "bidirectional"))
      (node (ref "V-THRUST_LED") (pin "P$2") (pinfunction "C_P$2") (pintype "passive"))
      (node (ref "V-THRUST_OUT") (pin "P$2") (pinfunction "P$2_P$2") (pintype "bidirectional"))
      (node (ref "V-THRUST_VOLAGE") (pin "P$3") (pinfunction "GND_P$3") (pintype "bidirectional"))
      (node (ref "WATER") (pin "2") (pinfunction "2_2") (pintype "passive"))
    )
    (net (code "47") (name "Net-(3V3_LED-A)") (class "Default")
      (node (ref "3V3_LED") (pin "P$1") (pinfunction "A_P$1") (pintype "passive"))
      (node (ref "R34") (pin "1") (pinfunction "1_1") (pintype "passive"))
    )
    (net (code "48") (name "Net-(5V_CURR_ADC-VIN)") (class "Default")
      (node (ref "5V_CURR_ADC") (pin "P$4") (pinfunction "VIN_P$4") (pintype "bidirectional"))
      (node (ref "U$2") (pin "P$7") (pinfunction "VIOUT_P$7") (pintype "bidirectional"))
    )
    (net (code "49") (name "Net-(5V_LED-A)") (class "Default")
      (node (ref "5V_LED") (pin "P$1") (pinfunction "A_P$1") (pintype "passive"))
      (node (ref "R31") (pin "1") (pinfunction "1_1") (pintype "passive"))
    )
    (net (code "50") (name "Net-(5V_PG-PadA)") (class "Default")
      (node (ref "5V_PG") (pin "A") (pinfunction "A_A") (pintype "passive"))
      (node (ref "R2") (pin "1") (pinfunction "1_1") (pintype "passive"))
    )
    (net (code "51") (name "Net-(5V_REG-BIAS)") (class "Default")
      (node (ref "5V_REG") (pin "1") (pinfunction "BIAS_1") (pintype "bidirectional"))
      (node (ref "C2") (pin "1") (pinfunction "1_1") (pintype "passive"))
      (node (ref "C42") (pin "1") (pinfunction "1_1") (pintype "passive"))
      (node (ref "C61") (pin "1") (pinfunction "1_1") (pintype "passive"))
      (node (ref "C62") (pin "P$1") (pinfunction "+_P$1") (pintype "passive"))
      (node (ref "L1") (pin "P$2") (pinfunction "2_P$2") (pintype "passive"))
      (node (ref "R23") (pin "2") (pinfunction "2_2") (pintype "passive"))
      (node (ref "U$2") (pin "P$1") (pinfunction "IP+_P$1") (pintype "bidirectional"))
      (node (ref "U$2") (pin "P$2") (pinfunction "IP+_P$2") (pintype "bidirectional"))
      (node (ref "U$2") (pin "P$8") (pinfunction "VCC_P$8") (pintype "bidirectional"))
    )
    (net (code "52") (name "Net-(5V_REG-BST)") (class "Default")
      (node (ref "5V_REG") (pin "3") (pinfunction "BST_3") (pintype "bidirectional"))
      (node (ref "C65") (pin "1") (pinfunction "1_1") (pintype "passive"))
    )
    (net (code "53") (name "Net-(5V_REG-FB)") (class "Default")
      (node (ref "5V_REG") (pin "20") (pinfunction "FB_20") (pintype "bidirectional"))
      (node (ref "C42") (pin "2") (pinfunction "2_2") (pintype "passive"))
      (node (ref "R23") (pin "1") (pinfunction "1_1") (pintype "passive"))
      (node (ref "R24") (pin "2") (pinfunction "2_2") (pintype "passive"))
    )
    (net (code "54") (name "Net-(5V_REG-INTV-CC)") (class "Default")
      (node (ref "5V_REG") (pin "2") (pinfunction "INTV-CC_2") (pintype "bidirectional"))
      (node (ref "C63") (pin "1") (pinfunction "1_1") (pintype "passive"))
    )
    (net (code "55") (name "Net-(5V_REG-PG)") (class "Default")
      (node (ref "5V_REG") (pin "19") (pinfunction "PG_19") (pintype "bidirectional"))
      (node (ref "R3") (pin "1") (pinfunction "1_1") (pintype "passive"))
      (node (ref "U$1") (pin "P$2") (pinfunction "G_P$2") (pintype "bidirectional"))
    )
    (net (code "56") (name "Net-(5V_REG-RT)") (class "Default")
      (node (ref "5V_REG") (pin "15") (pinfunction "RT_15") (pintype "bidirectional"))
      (node (ref "R17") (pin "2") (pinfunction "2_2") (pintype "passive"))
    )
    (net (code "57") (name "Net-(5V_VOLTAGE-IN+)") (class "Default")
      (node (ref "5V_VOLTAGE") (pin "P$1") (pinfunction "IN+_P$1") (pintype "bidirectional"))
      (node (ref "5V_VOLTAGE") (pin "P$2") (pinfunction "IN-_P$2") (pintype "bidirectional"))
      (node (ref "R35") (pin "2") (pinfunction "2_2") (pintype "passive"))
    )
    (net (code "58") (name "Net-(12V_CURR_ADC-VIN)") (class "Default")
      (node (ref "12V_CURR_ADC") (pin "P$4") (pinfunction "VIN_P$4") (pintype "bidirectional"))
      (node (ref "U$35") (pin "P$7") (pinfunction "VIOUT_P$7") (pintype "bidirectional"))
    )
    (net (code "59") (name "Net-(12V_LED-A)") (class "Default")
      (node (ref "12V_LED") (pin "P$1") (pinfunction "A_P$1") (pintype "passive"))
      (node (ref "R33") (pin "1") (pinfunction "1_1") (pintype "passive"))
    )
    (net (code "60") (name "Net-(12V_REG-BIAS)") (class "Default")
      (node (ref "12V_REG") (pin "1") (pinfunction "BIAS_1") (pintype "bidirectional"))
      (node (ref "C28") (pin "1") (pinfunction "1_1") (pintype "passive"))
      (node (ref "C35") (pin "1") (pinfunction "1_1") (pintype "passive"))
      (node (ref "C36") (pin "P$1") (pinfunction "+_P$1") (pintype "passive"))
      (node (ref "L2") (pin "P$2") (pinfunction "2_P$2") (pintype "passive"))
      (node (ref "R15") (pin "2") (pinfunction "2_2") (pintype "passive"))
      (node (ref "U$35") (pin "P$1") (pinfunction "IP+_P$1") (pintype "bidirectional"))
      (node (ref "U$35") (pin "P$2") (pinfunction "IP+_P$2") (pintype "bidirectional"))
    )
    (net (code "61") (name "Net-(12V_REG-BST)") (class "Default")
      (node (ref "12V_REG") (pin "3") (pinfunction "BST_3") (pintype "bidirectional"))
      (node (ref "C41") (pin "1") (pinfunction "1_1") (pintype "passive"))
    )
    (net (code "62") (name "Net-(12V_REG-FB)") (class "Default")
      (node (ref "12V_REG") (pin "20") (pinfunction "FB_20") (pintype "bidirectional"))
      (node (ref "C28") (pin "2") (pinfunction "2_2") (pintype "passive"))
      (node (ref "R15") (pin "1") (pinfunction "1_1") (pintype "passive"))
      (node (ref "R16") (pin "2") (pinfunction "2_2") (pintype "passive"))
    )
    (net (code "63") (name "Net-(12V_REG-INTV-CC)") (class "Default")
      (node (ref "12V_REG") (pin "2") (pinfunction "INTV-CC_2") (pintype "bidirectional"))
      (node (ref "C39") (pin "1") (pinfunction "1_1") (pintype "passive"))
    )
    (net (code "64") (name "Net-(12V_REG-PG)") (class "Default")
      (node (ref "12V_REG") (pin "19") (pinfunction "PG_19") (pintype "bidirectional"))
      (node (ref "R40") (pin "1") (pinfunction "1_1") (pintype "passive"))
      (node (ref "U$66") (pin "P$2") (pinfunction "G_P$2") (pintype "bidirectional"))
    )
    (net (code "65") (name "Net-(12V_REG-RT)") (class "Default")
      (node (ref "12V_REG") (pin "15") (pinfunction "RT_15") (pintype "bidirectional"))
      (node (ref "R14") (pin "2") (pinfunction "2_2") (pintype "passive"))
    )
    (net (code "66") (name "Net-(12V_VOLTAGE-IN+)") (class "Default")
      (node (ref "12V_VOLTAGE") (pin "P$1") (pinfunction "IN+_P$1") (pintype "bidirectional"))
      (node (ref "12V_VOLTAGE") (pin "P$2") (pinfunction "IN-_P$2") (pintype "bidirectional"))
      (node (ref "R25") (pin "2") (pinfunction "2_2") (pintype "passive"))
    )
    (net (code "67") (name "Net-(BATTERY_LED-A)") (class "Default")
      (node (ref "BATTERY_LED") (pin "P$1") (pinfunction "A_P$1") (pintype "passive"))
      (node (ref "R29") (pin "1") (pinfunction "1_1") (pintype "passive"))
    )
    (net (code "68") (name "Net-(I2C_SHIFT-EN)") (class "Default")
      (node (ref "C23") (pin "1") (pinfunction "1_1") (pintype "passive"))
      (node (ref "I2C_SHIFT") (pin "P$7") (pinfunction "VREF2_P$7") (pintype "bidirectional"))
      (node (ref "I2C_SHIFT") (pin "P$8") (pinfunction "EN_P$8") (pintype "bidirectional"))
      (node (ref "R12") (pin "1") (pinfunction "1_1") (pintype "passive"))
    )
    (net (code "69") (name "Net-(IC1A-I1)") (class "Default")
      (node (ref "IC1") (pin "2") (pinfunction "I1_2") (pintype "input"))
      (node (ref "R51") (pin "2") (pinfunction "2_2") (pintype "passive"))
      (node (ref "TH_DISABLE") (pin "1") (pinfunction "1_1") (pintype "passive"))
      (node (ref "T_FUSE") (pin "2") (pinfunction "2_2") (pintype "passive"))
    )
    (net (code "70") (name "Net-(IC2A-+IN)") (class "Default")
      (node (ref "IC2") (pin "3") (pinfunction "+IN_3") (pintype "input"))
      (node (ref "R59") (pin "2") (pinfunction "S_2") (pintype "passive"))
    )
    (net (code "71") (name "Net-(IC2A--IN)") (class "Default")
      (node (ref "IC2") (pin "2") (pinfunction "-IN_2") (pintype "input"))
      (node (ref "IC2") (pin "7") (pinfunction "OUT_7") (pintype "output"))
      (node (ref "R52") (pin "1") (pinfunction "1_1") (pintype "passive"))
    )
    (net (code "72") (name "Net-(IC2A-OUT)") (class "Default")
      (node (ref "IC2") (pin "1") (pinfunction "OUT_1") (pintype "output"))
      (node (ref "SK_DISABLE1") (pin "1") (pinfunction "1_1") (pintype "passive"))
    )
    (net (code "73") (name "Net-(IC2B-+IN)") (class "Default")
      (node (ref "IC2") (pin "5") (pinfunction "+IN_5") (pintype "input"))
      (node (ref "R57") (pin "1") (pinfunction "1_1") (pintype "passive"))
      (node (ref "R58") (pin "2") (pinfunction "2_2") (pintype "passive"))
    )
    (net (code "74") (name "Net-(IC2B--IN)") (class "Default")
      (node (ref "IC2") (pin "6") (pinfunction "-IN_6") (pintype "input"))
      (node (ref "R52") (pin "2") (pinfunction "2_2") (pintype "passive"))
      (node (ref "R54") (pin "1") (pinfunction "1_1") (pintype "passive"))
    )
    (net (code "75") (name "Net-(IC3A-I0)") (class "Default")
      (node (ref "C73") (pin "1") (pinfunction "1_1") (pintype "passive"))
      (node (ref "IC3") (pin "1") (pinfunction "I0_1") (pintype "input"))
      (node (ref "R45") (pin "1") (pinfunction "1_1") (pintype "passive"))
      (node (ref "R46") (pin "2") (pinfunction "2_2") (pintype "passive"))
      (node (ref "SK_DISABLE") (pin "1") (pinfunction "1_1") (pintype "passive"))
    )
    (net (code "76") (name "Net-(IC4A-I0)") (class "Default")
      (node (ref "FAULT1") (pin "2") (pinfunction "2_2") (pintype "passive"))
      (node (ref "FAULT1_DISABLE") (pin "1") (pinfunction "1_1") (pintype "passive"))
      (node (ref "IC4") (pin "1") (pinfunction "I0_1") (pintype "input"))
      (node (ref "R60") (pin "2") (pinfunction "2_2") (pintype "passive"))
    )
    (net (code "77") (name "Net-(IC4A-I1)") (class "Default")
      (node (ref "FAULT2") (pin "1") (pinfunction "1_1") (pintype "passive"))
      (node (ref "IC4") (pin "2") (pinfunction "I1_2") (pintype "input"))
      (node (ref "R61") (pin "1") (pinfunction "1_1") (pintype "passive"))
    )
    (net (code "78") (name "Net-(L1-1)") (class "Default")
      (node (ref "5V_REG") (pin "21") (pinfunction "SW_21") (pintype "bidirectional"))
      (node (ref "5V_REG") (pin "22") (pinfunction "SW_22") (pintype "bidirectional"))
      (node (ref "5V_REG") (pin "8") (pinfunction "SW_8") (pintype "bidirectional"))
      (node (ref "5V_REG") (pin "9") (pinfunction "SW_9") (pintype "bidirectional"))
      (node (ref "C65") (pin "2") (pinfunction "2_2") (pintype "passive"))
      (node (ref "L1") (pin "P$1") (pinfunction "1_P$1") (pintype "passive"))
    )
    (net (code "79") (name "Net-(L2-1)") (class "Default")
      (node (ref "12V_REG") (pin "21") (pinfunction "SW_21") (pintype "bidirectional"))
      (node (ref "12V_REG") (pin "22") (pinfunction "SW_22") (pintype "bidirectional"))
      (node (ref "12V_REG") (pin "8") (pinfunction "SW_8") (pintype "bidirectional"))
      (node (ref "12V_REG") (pin "9") (pinfunction "SW_9") (pintype "bidirectional"))
      (node (ref "C41") (pin "2") (pinfunction "2_2") (pintype "passive"))
      (node (ref "L2") (pin "P$1") (pinfunction "1_P$1") (pintype "passive"))
    )
    (net (code "80") (name "Net-(LED2-PadA)") (class "Default")
      (node (ref "LED2") (pin "A") (pinfunction "A_A") (pintype "passive"))
      (node (ref "R38") (pin "1") (pinfunction "1_1") (pintype "passive"))
    )
    (net (code "81") (name "Net-(N1-D)") (class "Default")
      (node (ref "D1") (pin "A") (pinfunction "A_A") (pintype "passive"))
      (node (ref "N1") (pin "3") (pinfunction "D_3") (pintype "bidirectional"))
      (node (ref "R42") (pin "2") (pinfunction "2_2") (pintype "passive"))
    )
    (net (code "82") (name "Net-(ON_INDICATOR-PadA)") (class "Default")
      (node (ref "ON_INDICATOR") (pin "A") (pinfunction "A_A") (pintype "passive"))
      (node (ref "R47") (pin "1") (pinfunction "1_1") (pintype "passive"))
      (node (ref "R48") (pin "1") (pinfunction "1_1") (pintype "passive"))
    )
    (net (code "83") (name "Net-(Q1-G)") (class "Default")
      (node (ref "Q1") (pin "1") (pinfunction "G_1") (pintype "passive"))
      (node (ref "R41") (pin "1") (pinfunction "1_1") (pintype "passive"))
      (node (ref "R42") (pin "1") (pinfunction "1_1") (pintype "passive"))
    )
    (net (code "84") (name "Net-(R19-Pad1)") (class "Default")
      (node (ref "R19") (pin "1") (pinfunction "1_1") (pintype "passive"))
      (node (ref "U$25") (pin "AA") (pinfunction "A_AA") (pintype "bidirectional"))
      (node (ref "U$25") (pin "AB") (pinfunction "A_AB") (pintype "bidirectional"))
    )
    (net (code "85") (name "Net-(R26-Pad2)") (class "Default")
      (node (ref "R26") (pin "2") (pinfunction "2_2") (pintype "passive"))
      (node (ref "R27") (pin "2") (pinfunction "2_2") (pintype "passive"))
      (node (ref "U$62") (pin "P$2") (pinfunction "P$2_P$2") (pintype "bidirectional"))
    )
    (net (code "86") (name "Net-(R36-Pad2)") (class "Default")
      (node (ref "R36") (pin "2") (pinfunction "2_2") (pintype "passive"))
      (node (ref "R37") (pin "2") (pinfunction "2_2") (pintype "passive"))
      (node (ref "U$63") (pin "P$2") (pinfunction "P$2_P$2") (pintype "bidirectional"))
    )
    (net (code "87") (name "Net-(R54-Pad2)") (class "Default")
      (node (ref "R54") (pin "2") (pinfunction "2_2") (pintype "passive"))
      (node (ref "R55") (pin "2") (pinfunction "2_2") (pintype "passive"))
      (node (ref "R56") (pin "1") (pinfunction "1_1") (pintype "passive"))
    )
    (net (code "88") (name "Net-(R56-Pad2)") (class "Default")
      (node (ref "R56") (pin "2") (pinfunction "2_2") (pintype "passive"))
      (node (ref "WATER") (pin "1") (pinfunction "1_1") (pintype "passive"))
    )
    (net (code "89") (name "Net-(RELAY-OUT_LED-A)") (class "Default")
      (node (ref "R20") (pin "1") (pinfunction "1_1") (pintype "passive"))
      (node (ref "RELAY-OUT_LED") (pin "P$1") (pinfunction "A_P$1") (pintype "passive"))
    )
    (net (code "90") (name "Net-(SHORE-FET-D)") (class "Default")
      (node (ref "R37") (pin "1") (pinfunction "1_1") (pintype "passive"))
      (node (ref "SHORE-FET") (pin "TAB") (pinfunction "D_TAB") (pintype "passive"))
      (node (ref "SHORE_IN") (pin "P$1") (pinfunction "P$1_P$1") (pintype "bidirectional"))
      (node (ref "U$57") (pin "P$2") (pinfunction "C_P$2") (pintype "passive"))
    )
    (net (code "91") (name "Net-(SHORE-FET-G)") (class "Default")
      (node (ref "C66") (pin "1") (pinfunction "1_1") (pintype "passive"))
      (node (ref "R36") (pin "1") (pinfunction "1_1") (pintype "passive"))
      (node (ref "SHORE-FET") (pin "1") (pinfunction "G_1") (pintype "passive"))
    )
    (net (code "92") (name "Net-(SHORE_LED-A)") (class "Default")
      (node (ref "R39") (pin "1") (pinfunction "1_1") (pintype "passive"))
      (node (ref "SHORE_LED") (pin "P$1") (pinfunction "A_P$1") (pintype "passive"))
    )
    (net (code "93") (name "Net-(THRUSTER_CURR_ADC-COM)") (class "Default")
      (node (ref "R22") (pin "1") (pinfunction "1_1") (pintype "passive"))
      (node (ref "THRUSTER_CURR_ADC") (pin "11") (pinfunction "COM_11") (pintype "bidirectional"))
    )
    (net (code "94") (name "Net-(U$1-D)") (class "Default")
      (node (ref "R2") (pin "2") (pinfunction "2_2") (pintype "passive"))
      (node (ref "U$1") (pin "P$3") (pinfunction "D_P$3") (pintype "bidirectional"))
    )
    (net (code "95") (name "Net-(U$2-FILTER)") (class "Default")
      (node (ref "C3") (pin "1") (pinfunction "1_1") (pintype "passive"))
      (node (ref "U$2") (pin "P$6") (pinfunction "FILTER_P$6") (pintype "bidirectional"))
    )
    (net (code "96") (name "Net-(U$2-IP--PadP$3)") (class "Default")
      (node (ref "U$2") (pin "P$3") (pinfunction "IP-_P$3") (pintype "bidirectional"))
      (node (ref "U$2") (pin "P$4") (pinfunction "IP-_P$4") (pintype "bidirectional"))
      (node (ref "U$20") (pin "P$1") (pinfunction "P$1_P$1") (pintype "bidirectional"))
    )
    (net (code "97") (name "Net-(U$3-~{RESET})") (class "Default")
      (node (ref "R1") (pin "1") (pinfunction "1_1") (pintype "passive"))
      (node (ref "U$3") (pin "2-5") (pinfunction "~{RESET}_2-5") (pintype "bidirectional"))
    )
    (net (code "98") (name "Net-(U$4-FILTER)") (class "Default")
      (node (ref "C6") (pin "1") (pinfunction "1_1") (pintype "passive"))
      (node (ref "U$4") (pin "P$6") (pinfunction "FILTER_P$6") (pintype "bidirectional"))
    )
    (net (code "99") (name "Net-(U$4-IP--PadP$3)") (class "Default")
      (node (ref "U$4") (pin "P$3") (pinfunction "IP-_P$3") (pintype "bidirectional"))
      (node (ref "U$4") (pin "P$4") (pinfunction "IP-_P$4") (pintype "bidirectional"))
      (node (ref "U$6") (pin "P$1") (pinfunction "P$1_P$1") (pintype "bidirectional"))
    )
    (net (code "100") (name "Net-(U$8-FILTER)") (class "Default")
      (node (ref "C9") (pin "1") (pinfunction "1_1") (pintype "passive"))
      (node (ref "U$8") (pin "P$6") (pinfunction "FILTER_P$6") (pintype "bidirectional"))
    )
    (net (code "101") (name "Net-(U$8-IP--PadP$3)") (class "Default")
      (node (ref "U$8") (pin "P$3") (pinfunction "IP-_P$3") (pintype "bidirectional"))
      (node (ref "U$8") (pin "P$4") (pinfunction "IP-_P$4") (pintype "bidirectional"))
      (node (ref "U$9") (pin "P$1") (pinfunction "P$1_P$1") (pintype "bidirectional"))
    )
    (net (code "102") (name "Net-(U$10-C)") (class "Default")
      (node (ref "C58") (pin "1") (pinfunction "1_1") (pintype "passive"))
      (node (ref "THRUST8") (pin "P$4") (pinfunction "P$4_P$4") (pintype "bidirectional"))
      (node (ref "U$10") (pin "P$2") (pinfunction "C_P$2") (pintype "passive"))
      (node (ref "U$40") (pin "P$2") (pinfunction "P$2_P$2") (pintype "bidirectional"))
    )
    (net (code "103") (name "Net-(U$11-FILTER)") (class "Default")
      (node (ref "C12") (pin "1") (pinfunction "1_1") (pintype "passive"))
      (node (ref "U$11") (pin "P$6") (pinfunction "FILTER_P$6") (pintype "bidirectional"))
    )
    (net (code "104") (name "Net-(U$11-IP--PadP$3)") (class "Default")
      (node (ref "U$11") (pin "P$3") (pinfunction "IP-_P$3") (pintype "bidirectional"))
      (node (ref "U$11") (pin "P$4") (pinfunction "IP-_P$4") (pintype "bidirectional"))
      (node (ref "U$12") (pin "P$1") (pinfunction "P$1_P$1") (pintype "bidirectional"))
    )
    (net (code "105") (name "Net-(U$13-C)") (class "Default")
      (node (ref "C30") (pin "1") (pinfunction "1_1") (pintype "passive"))
      (node (ref "THRUST6") (pin "P$4") (pinfunction "P$4_P$4") (pintype "bidirectional"))
      (node (ref "U$13") (pin "P$2") (pinfunction "C_P$2") (pintype "passive"))
      (node (ref "U$27") (pin "P$2") (pinfunction "P$2_P$2") (pintype "bidirectional"))
    )
    (net (code "106") (name "Net-(U$14-FILTER)") (class "Default")
      (node (ref "C15") (pin "1") (pinfunction "1_1") (pintype "passive"))
      (node (ref "U$14") (pin "P$6") (pinfunction "FILTER_P$6") (pintype "bidirectional"))
    )
    (net (code "107") (name "Net-(U$14-IP--PadP$3)") (class "Default")
      (node (ref "U$14") (pin "P$3") (pinfunction "IP-_P$3") (pintype "bidirectional"))
      (node (ref "U$14") (pin "P$4") (pinfunction "IP-_P$4") (pintype "bidirectional"))
      (node (ref "U$15") (pin "P$1") (pinfunction "P$1_P$1") (pintype "bidirectional"))
    )
    (net (code "108") (name "Net-(U$16-C)") (class "Default")
      (node (ref "C55") (pin "1") (pinfunction "1_1") (pintype "passive"))
      (node (ref "THRUST7") (pin "P$4") (pinfunction "P$4_P$4") (pintype "bidirectional"))
      (node (ref "U$16") (pin "P$2") (pinfunction "C_P$2") (pintype "passive"))
      (node (ref "U$37") (pin "P$2") (pinfunction "P$2_P$2") (pintype "bidirectional"))
    )
    (net (code "109") (name "Net-(U$17-FILTER)") (class "Default")
      (node (ref "C18") (pin "1") (pinfunction "1_1") (pintype "passive"))
      (node (ref "U$17") (pin "P$6") (pinfunction "FILTER_P$6") (pintype "bidirectional"))
    )
    (net (code "110") (name "Net-(U$17-IP--PadP$3)") (class "Default")
      (node (ref "U$17") (pin "P$3") (pinfunction "IP-_P$3") (pintype "bidirectional"))
      (node (ref "U$17") (pin "P$4") (pinfunction "IP-_P$4") (pintype "bidirectional"))
      (node (ref "U$18") (pin "P$1") (pinfunction "P$1_P$1") (pintype "bidirectional"))
    )
    (net (code "111") (name "Net-(U$19-FILTER)") (class "Default")
      (node (ref "C20") (pin "1") (pinfunction "1_1") (pintype "passive"))
      (node (ref "U$19") (pin "P$6") (pinfunction "FILTER_P$6") (pintype "bidirectional"))
    )
    (net (code "112") (name "Net-(U$19-IP--PadP$3)") (class "Default")
      (node (ref "U$19") (pin "P$3") (pinfunction "IP-_P$3") (pintype "bidirectional"))
      (node (ref "U$19") (pin "P$4") (pinfunction "IP-_P$4") (pintype "bidirectional"))
      (node (ref "U$5") (pin "P$1") (pinfunction "P$1_P$1") (pintype "bidirectional"))
      (node (ref "U$5") (pin "P$2") (pinfunction "P$1_P$2") (pintype "bidirectional"))
    )
    (net (code "113") (name "Net-(U$19-VIOUT)") (class "Default")
      (node (ref "U$19") (pin "P$7") (pinfunction "VIOUT_P$7") (pintype "bidirectional"))
      (node (ref "V-THRUST_CURR_ADC") (pin "P$4") (pinfunction "VIN_P$4") (pintype "bidirectional"))
    )
    (net (code "114") (name "Net-(U$22-C)") (class "Default")
      (node (ref "C21") (pin "1") (pinfunction "1_1") (pintype "passive"))
      (node (ref "THRUST5") (pin "P$4") (pinfunction "P$4_P$4") (pintype "bidirectional"))
      (node (ref "U$18") (pin "P$2") (pinfunction "P$2_P$2") (pintype "bidirectional"))
      (node (ref "U$22") (pin "P$2") (pinfunction "C_P$2") (pintype "passive"))
    )
    (net (code "115") (name "Net-(U$23-FILTER)") (class "Default")
      (node (ref "C29") (pin "1") (pinfunction "1_1") (pintype "passive"))
      (node (ref "U$23") (pin "P$6") (pinfunction "FILTER_P$6") (pintype "bidirectional"))
    )
    (net (code "116") (name "Net-(U$23-IP--PadP$3)") (class "Default")
      (node (ref "U$23") (pin "P$3") (pinfunction "IP-_P$3") (pintype "bidirectional"))
      (node (ref "U$23") (pin "P$4") (pinfunction "IP-_P$4") (pintype "bidirectional"))
      (node (ref "U$27") (pin "P$1") (pinfunction "P$1_P$1") (pintype "bidirectional"))
    )
    (net (code "117") (name "Net-(U$26-C)") (class "Default")
      (node (ref "C13") (pin "1") (pinfunction "1_1") (pintype "passive"))
      (node (ref "THRUST3") (pin "P$4") (pinfunction "P$4_P$4") (pintype "bidirectional"))
      (node (ref "U$12") (pin "P$2") (pinfunction "P$2_P$2") (pintype "bidirectional"))
      (node (ref "U$26") (pin "P$2") (pinfunction "C_P$2") (pintype "passive"))
    )
    (net (code "118") (name "Net-(U$28-C)") (class "Default")
      (node (ref "C16") (pin "1") (pinfunction "1_1") (pintype "passive"))
      (node (ref "THRUST4") (pin "P$4") (pinfunction "P$4_P$4") (pintype "bidirectional"))
      (node (ref "U$15") (pin "P$2") (pinfunction "P$2_P$2") (pintype "bidirectional"))
      (node (ref "U$28") (pin "P$2") (pinfunction "C_P$2") (pintype "passive"))
    )
    (net (code "119") (name "Net-(U$29-FILTER)") (class "Default")
      (node (ref "C37") (pin "1") (pinfunction "1_1") (pintype "passive"))
      (node (ref "U$29") (pin "P$6") (pinfunction "FILTER_P$6") (pintype "bidirectional"))
    )
    (net (code "120") (name "Net-(U$29-IP--PadP$3)") (class "Default")
      (node (ref "U$29") (pin "P$3") (pinfunction "IP-_P$3") (pintype "bidirectional"))
      (node (ref "U$29") (pin "P$4") (pinfunction "IP-_P$4") (pintype "bidirectional"))
      (node (ref "U$37") (pin "P$1") (pinfunction "P$1_P$1") (pintype "bidirectional"))
    )
    (net (code "121") (name "Net-(U$30-C)") (class "Default")
      (node (ref "C10") (pin "1") (pinfunction "1_1") (pintype "passive"))
      (node (ref "THRUST2") (pin "P$4") (pinfunction "P$4_P$4") (pintype "bidirectional"))
      (node (ref "U$30") (pin "P$2") (pinfunction "C_P$2") (pintype "passive"))
      (node (ref "U$9") (pin "P$2") (pinfunction "P$2_P$2") (pintype "bidirectional"))
    )
    (net (code "122") (name "Net-(U$31-C)") (class "Default")
      (node (ref "C54") (pin "1") (pinfunction "1_1") (pintype "passive"))
      (node (ref "THRUST1") (pin "P$4") (pinfunction "P$4_P$4") (pintype "bidirectional"))
      (node (ref "U$31") (pin "P$2") (pinfunction "C_P$2") (pintype "passive"))
      (node (ref "U$6") (pin "P$2") (pinfunction "P$2_P$2") (pintype "bidirectional"))
    )
    (net (code "123") (name "Net-(U$35-FILTER)") (class "Default")
      (node (ref "C31") (pin "1") (pinfunction "1_1") (pintype "passive"))
      (node (ref "U$35") (pin "P$6") (pinfunction "FILTER_P$6") (pintype "bidirectional"))
    )
    (net (code "124") (name "Net-(U$35-IP--PadP$3)") (class "Default")
      (node (ref "U$35") (pin "P$3") (pinfunction "IP-_P$3") (pintype "bidirectional"))
      (node (ref "U$35") (pin "P$4") (pinfunction "IP-_P$4") (pintype "bidirectional"))
      (node (ref "U$36") (pin "P$1") (pinfunction "P$1_P$1") (pintype "bidirectional"))
    )
    (net (code "125") (name "Net-(U$39-FILTER)") (class "Default")
      (node (ref "C57") (pin "1") (pinfunction "1_1") (pintype "passive"))
      (node (ref "U$39") (pin "P$6") (pinfunction "FILTER_P$6") (pintype "bidirectional"))
    )
    (net (code "126") (name "Net-(U$39-IP--PadP$3)") (class "Default")
      (node (ref "U$39") (pin "P$3") (pinfunction "IP-_P$3") (pintype "bidirectional"))
      (node (ref "U$39") (pin "P$4") (pinfunction "IP-_P$4") (pintype "bidirectional"))
      (node (ref "U$40") (pin "P$1") (pinfunction "P$1_P$1") (pintype "bidirectional"))
    )
    (net (code "127") (name "Net-(U$45-GND)") (class "Default")
      (node (ref "C32") (pin "2") (pinfunction "2_2") (pintype "passive"))
      (node (ref "CPU_ON") (pin "P$2") (pinfunction "P$2_P$2") (pintype "bidirectional"))
      (node (ref "U$45") (pin "P$3") (pinfunction "GND_P$3") (pintype "bidirectional"))
      (node (ref "U$59") (pin "P$1") (pinfunction "A_P$1") (pintype "passive"))
    )
    (net (code "128") (name "Net-(U$45-IN)") (class "Default")
      (node (ref "C32") (pin "1") (pinfunction "1_1") (pintype "passive"))
      (node (ref "R18") (pin "2") (pinfunction "2_2") (pintype "passive"))
      (node (ref "U$45") (pin "P$2") (pinfunction "IN_P$2") (pintype "bidirectional"))
    )
    (net (code "129") (name "Net-(U$59-C)") (class "Default")
      (node (ref "CPU_ON") (pin "P$1") (pinfunction "P$1_P$1") (pintype "bidirectional"))
      (node (ref "R18") (pin "1") (pinfunction "1_1") (pintype "passive"))
      (node (ref "R21") (pin "1") (pinfunction "1_1") (pintype "passive"))
      (node (ref "U$59") (pin "P$2") (pinfunction "C_P$2") (pintype "passive"))
    )
    (net (code "130") (name "Net-(U$60-C)") (class "Default")
      (node (ref "BATTERY_IN") (pin "P$1") (pinfunction "P$1_P$1") (pintype "bidirectional"))
      (node (ref "R27") (pin "1") (pinfunction "1_1") (pintype "passive"))
      (node (ref "U$60") (pin "P$2") (pinfunction "C_P$2") (pintype "passive"))
      (node (ref "U$61") (pin "TAB") (pinfunction "D_TAB") (pintype "passive"))
    )
    (net (code "131") (name "Net-(U$61-G)") (class "Default")
      (node (ref "C64") (pin "1") (pinfunction "1_1") (pintype "passive"))
      (node (ref "R26") (pin "1") (pinfunction "1_1") (pintype "passive"))
      (node (ref "U$61") (pin "1") (pinfunction "G_1") (pintype "passive"))
    )
    (net (code "132") (name "Net-(U$66-D)") (class "Default")
      (node (ref "R38") (pin "2") (pinfunction "2_2") (pintype "passive"))
      (node (ref "U$66") (pin "P$3") (pinfunction "D_P$3") (pintype "bidirectional"))
    )
    (net (code "133") (name "Net-(U2-ADJ)") (class "Default")
      (node (ref "R43") (pin "1") (pinfunction "1_1") (pintype "passive"))
      (node (ref "R44") (pin "2") (pinfunction "2_2") (pintype "passive"))
      (node (ref "U2") (pin "2") (pinfunction "ADJ_2") (pintype "bidirectional"))
    )
    (net (code "134") (name "Net-(U2-REF{slash}BYP)") (class "Default")
      (node (ref "C70") (pin "1") (pinfunction "1_1") (pintype "passive"))
      (node (ref "U2") (pin "1") (pinfunction "REF/BYP_1") (pintype "bidirectional"))
    )
    (net (code "135") (name "Net-(U3-ADJ)") (class "Default")
      (node (ref "R49") (pin "1") (pinfunction "1_1") (pintype "passive"))
      (node (ref "R50") (pin "2") (pinfunction "2_2") (pintype "passive"))
      (node (ref "U3") (pin "2") (pinfunction "ADJ_2") (pintype "bidirectional"))
    )
    (net (code "136") (name "Net-(U3-REF{slash}BYP)") (class "Default")
      (node (ref "C74") (pin "1") (pinfunction "1_1") (pintype "passive"))
      (node (ref "U3") (pin "1") (pinfunction "REF/BYP_1") (pintype "bidirectional"))
    )
    (net (code "137") (name "Net-(V-THRUST_LED-A)") (class "Default")
      (node (ref "R32") (pin "1") (pinfunction "1_1") (pintype "passive"))
      (node (ref "V-THRUST_LED") (pin "P$1") (pinfunction "A_P$1") (pintype "passive"))
    )
    (net (code "138") (name "Net-(V-THRUST_VOLAGE-IN+)") (class "Default")
      (node (ref "R30") (pin "2") (pinfunction "2_2") (pintype "passive"))
      (node (ref "V-THRUST_VOLAGE") (pin "P$1") (pinfunction "IN+_P$1") (pintype "bidirectional"))
      (node (ref "V-THRUST_VOLAGE") (pin "P$2") (pinfunction "IN-_P$2") (pintype "bidirectional"))
    )
    (net (code "139") (name "ON_SW") (class "Default")
      (node (ref "D1") (pin "C") (pinfunction "C_C") (pintype "passive"))
      (node (ref "ON") (pin "3") (pinfunction "3_3") (pintype "passive"))
      (node (ref "ON") (pin "4") (pinfunction "4_4") (pintype "passive"))
      (node (ref "ON_SW") (pin "1") (pinfunction "1_1") (pintype "passive"))
    )
    (net (code "140") (name "RELAY-BATT") (class "Default")
      (node (ref "Q1") (pin "2") (pinfunction "S_2") (pintype "passive"))
      (node (ref "R29") (pin "2") (pinfunction "2_2") (pintype "passive"))
      (node (ref "R41") (pin "2") (pinfunction "2_2") (pintype "passive"))
      (node (ref "U$25") (pin "5A") (pinfunction "5_5A") (pintype "bidirectional"))
      (node (ref "U$25") (pin "5B") (pinfunction "5_5B") (pintype "bidirectional"))
      (node (ref "U$61") (pin "3") (pinfunction "S_3") (pintype "passive"))
    )
    (net (code "141") (name "RELAY-CTRL") (class "Default")
      (node (ref "C75") (pin "1") (pinfunction "1_1") (pintype "passive"))
      (node (ref "R49") (pin "2") (pinfunction "2_2") (pintype "passive"))
      (node (ref "U$25") (pin "BA") (pinfunction "B_BA") (pintype "bidirectional"))
      (node (ref "U$25") (pin "BB") (pinfunction "B_BB") (pintype "bidirectional"))
      (node (ref "U3") (pin "3") (pinfunction "OUT_3") (pintype "bidirectional"))
      (node (ref "U3") (pin "4") (pinfunction "OUT_4") (pintype "bidirectional"))
    )
    (net (code "142") (name "SOFT_KILL") (class "Default")
      (node (ref "R45") (pin "2") (pinfunction "2_2") (pintype "passive"))
    )
    (net (code "143") (name "VDD") (class "Default")
      (node (ref "C72") (pin "+") (pinfunction "+_+") (pintype "passive"))
      (node (ref "C76") (pin "+") (pinfunction "+_+") (pintype "passive"))
      (node (ref "Q1") (pin "3") (pinfunction "D_3") (pintype "passive"))
      (node (ref "R47") (pin "2") (pinfunction "2_2") (pintype "passive"))
      (node (ref "R48") (pin "2") (pinfunction "2_2") (pintype "passive"))
      (node (ref "U2") (pin "5") (pinfunction "IN_5") (pintype "bidirectional"))
      (node (ref "U2") (pin "6") (pinfunction "IN_6") (pintype "bidirectional"))
      (node (ref "U2") (pin "7") (pinfunction "SHDN_7") (pintype "bidirectional"))
      (node (ref "U3") (pin "5") (pinfunction "IN_5") (pintype "bidirectional"))
      (node (ref "U3") (pin "6") (pinfunction "IN_6") (pintype "bidirectional"))
      (node (ref "U3") (pin "7") (pinfunction "SHDN_7") (pintype "bidirectional"))
    )
    (net (code "144") (name "WATER") (class "Default")
      (node (ref "IC1") (pin "1") (pinfunction "I0_1") (pintype "input"))
      (node (ref "SK_DISABLE1") (pin "2") (pinfunction "2_2") (pintype "passive"))
    )
    (net (code "145") (name "unconnected-(5V_CURR_ADC-ALERT-PadP$2)") (class "Default")
      (node (ref "5V_CURR_ADC") (pin "P$2") (pinfunction "ALERT_P$2") (pintype "bidirectional"))
    )
    (net (code "146") (name "unconnected-(5V_REG-SYNC{slash}MODE-Pad17)") (class "Default")
      (node (ref "5V_REG") (pin "17") (pinfunction "SYNC/MODE_17") (pintype "bidirectional"))
    )
    (net (code "147") (name "unconnected-(5V_REG-TR{slash}SS-Pad16)") (class "Default")
      (node (ref "5V_REG") (pin "16") (pinfunction "TR/SS_16") (pintype "bidirectional"))
    )
    (net (code "148") (name "unconnected-(12V_CURR_ADC-ALERT-PadP$2)") (class "Default")
      (node (ref "12V_CURR_ADC") (pin "P$2") (pinfunction "ALERT_P$2") (pintype "bidirectional"))
    )
    (net (code "149") (name "unconnected-(12V_REG-SYNC{slash}MODE-Pad17)") (class "Default")
      (node (ref "12V_REG") (pin "17") (pinfunction "SYNC/MODE_17") (pintype "bidirectional"))
    )
    (net (code "150") (name "unconnected-(12V_REG-TR{slash}SS-Pad16)") (class "Default")
      (node (ref "12V_REG") (pin "16") (pinfunction "TR/SS_16") (pintype "bidirectional"))
    )
    (net (code "151") (name "unconnected-(U$3-PA2-Pad2-10)") (class "Default")
      (node (ref "U$3") (pin "2-10") (pinfunction "PA2_2-10") (pintype "bidirectional"))
    )
    (net (code "152") (name "unconnected-(U$3-PA3-Pad2-9)") (class "Default")
      (node (ref "U$3") (pin "2-9") (pinfunction "PA3_2-9") (pintype "bidirectional"))
    )
    (net (code "153") (name "unconnected-(U$3-PA4-Pad2-8)") (class "Default")
      (node (ref "U$3") (pin "2-8") (pinfunction "PA4_2-8") (pintype "bidirectional"))
    )
    (net (code "154") (name "unconnected-(U$3-PA5-Pad1-8)") (class "Default")
      (node (ref "U$3") (pin "1-8") (pinfunction "PA5_1-8") (pintype "bidirectional"))
    )
    (net (code "155") (name "unconnected-(U$3-PB2-Pad2-2)") (class "Default")
      (node (ref "U$3") (pin "2-2") (pinfunction "PB2_2-2") (pintype "bidirectional"))
    )
    (net (code "156") (name "unconnected-(U$3-PB3-Pad4-3)") (class "Default")
      (node (ref "U$3") (pin "4-3") (pinfunction "PB3_4-3") (pintype "bidirectional"))
    )
    (net (code "157") (name "unconnected-(U$3-PB6-Pad3-3)") (class "Default")
      (node (ref "U$3") (pin "3-3") (pinfunction "PB6_3-3") (pintype "bidirectional"))
    )
    (net (code "158") (name "unconnected-(U$3-PB7-Pad3-4)") (class "Default")
      (node (ref "U$3") (pin "3-4") (pinfunction "PB7_3-4") (pintype "bidirectional"))
    )
    (net (code "159") (name "unconnected-(U$3-PC4-Pad4-4)") (class "Default")
      (node (ref "U$3") (pin "4-4") (pinfunction "PC4_4-4") (pintype "bidirectional"))
    )
    (net (code "160") (name "unconnected-(U$3-PC5-Pad4-5)") (class "Default")
      (node (ref "U$3") (pin "4-5") (pinfunction "PC5_4-5") (pintype "bidirectional"))
    )
    (net (code "161") (name "unconnected-(U$3-PC6-Pad4-6)") (class "Default")
      (node (ref "U$3") (pin "4-6") (pinfunction "PC6_4-6") (pintype "bidirectional"))
    )
    (net (code "162") (name "unconnected-(U$3-PC7-Pad4-7)") (class "Default")
      (node (ref "U$3") (pin "4-7") (pinfunction "PC7_4-7") (pintype "bidirectional"))
    )
    (net (code "163") (name "unconnected-(U$3-PD6-Pad4-8)") (class "Default")
      (node (ref "U$3") (pin "4-8") (pinfunction "PD6_4-8") (pintype "bidirectional"))
    )
    (net (code "164") (name "unconnected-(U$3-PD7-Pad4-9)") (class "Default")
      (node (ref "U$3") (pin "4-9") (pinfunction "PD7_4-9") (pintype "bidirectional"))
    )
    (net (code "165") (name "unconnected-(U$3-PF0-Pad2-4)") (class "Default")
      (node (ref "U$3") (pin "2-4") (pinfunction "PF0_2-4") (pintype "bidirectional"))
    )
    (net (code "166") (name "unconnected-(U$3-PF1-Pad3-10)") (class "Default")
      (node (ref "U$3") (pin "3-10") (pinfunction "PF1_3-10") (pintype "bidirectional"))
    )
    (net (code "167") (name "unconnected-(U$3-PF2-Pad4-1)") (class "Default")
      (node (ref "U$3") (pin "4-1") (pinfunction "PF2_4-1") (pintype "bidirectional"))
    )
    (net (code "168") (name "unconnected-(U$3-PF3-Pad4-2)") (class "Default")
      (node (ref "U$3") (pin "4-2") (pinfunction "PF3_4-2") (pintype "bidirectional"))
    )
    (net (code "169") (name "unconnected-(U$3-PF4-Pad4-10)") (class "Default")
      (node (ref "U$3") (pin "4-10") (pinfunction "PF4_4-10") (pintype "bidirectional"))
    )
    (net (code "170") (name "unconnected-(U1-CH8-Pad15)") (class "Default")
      (node (ref "U1") (pin "15") (pinfunction "CH8_15") (pintype "bidirectional"))
    )
    (net (code "171") (name "unconnected-(U1-CH9-Pad16)") (class "Default")
      (node (ref "U1") (pin "16") (pinfunction "CH9_16") (pintype "bidirectional"))
    )
    (net (code "172") (name "unconnected-(U1-CH10-Pad17)") (class "Default")
      (node (ref "U1") (pin "17") (pinfunction "CH10_17") (pintype "bidirectional"))
    )
    (net (code "173") (name "unconnected-(U1-CH11-Pad18)") (class "Default")
      (node (ref "U1") (pin "18") (pinfunction "CH11_18") (pintype "bidirectional"))
    )
    (net (code "174") (name "unconnected-(U1-CH12-Pad19)") (class "Default")
      (node (ref "U1") (pin "19") (pinfunction "CH12_19") (pintype "bidirectional"))
    )
    (net (code "175") (name "unconnected-(U1-CH13-Pad20)") (class "Default")
      (node (ref "U1") (pin "20") (pinfunction "CH13_20") (pintype "bidirectional"))
    )
    (net (code "176") (name "unconnected-(U1-CH14-Pad21)") (class "Default")
      (node (ref "U1") (pin "21") (pinfunction "CH14_21") (pintype "bidirectional"))
    )
    (net (code "177") (name "unconnected-(U1-CH15-Pad22)") (class "Default")
      (node (ref "U1") (pin "22") (pinfunction "CH15_22") (pintype "bidirectional"))
    )
    (net (code "178") (name "unconnected-(V-THRUST_CURR_ADC-ALERT-PadP$2)") (class "Default")
      (node (ref "V-THRUST_CURR_ADC") (pin "P$2") (pinfunction "ALERT_P$2") (pintype "bidirectional"))
    )
  )
)
